# TOP.net
KiCad netlist of a schematic drawn in Altium Designer
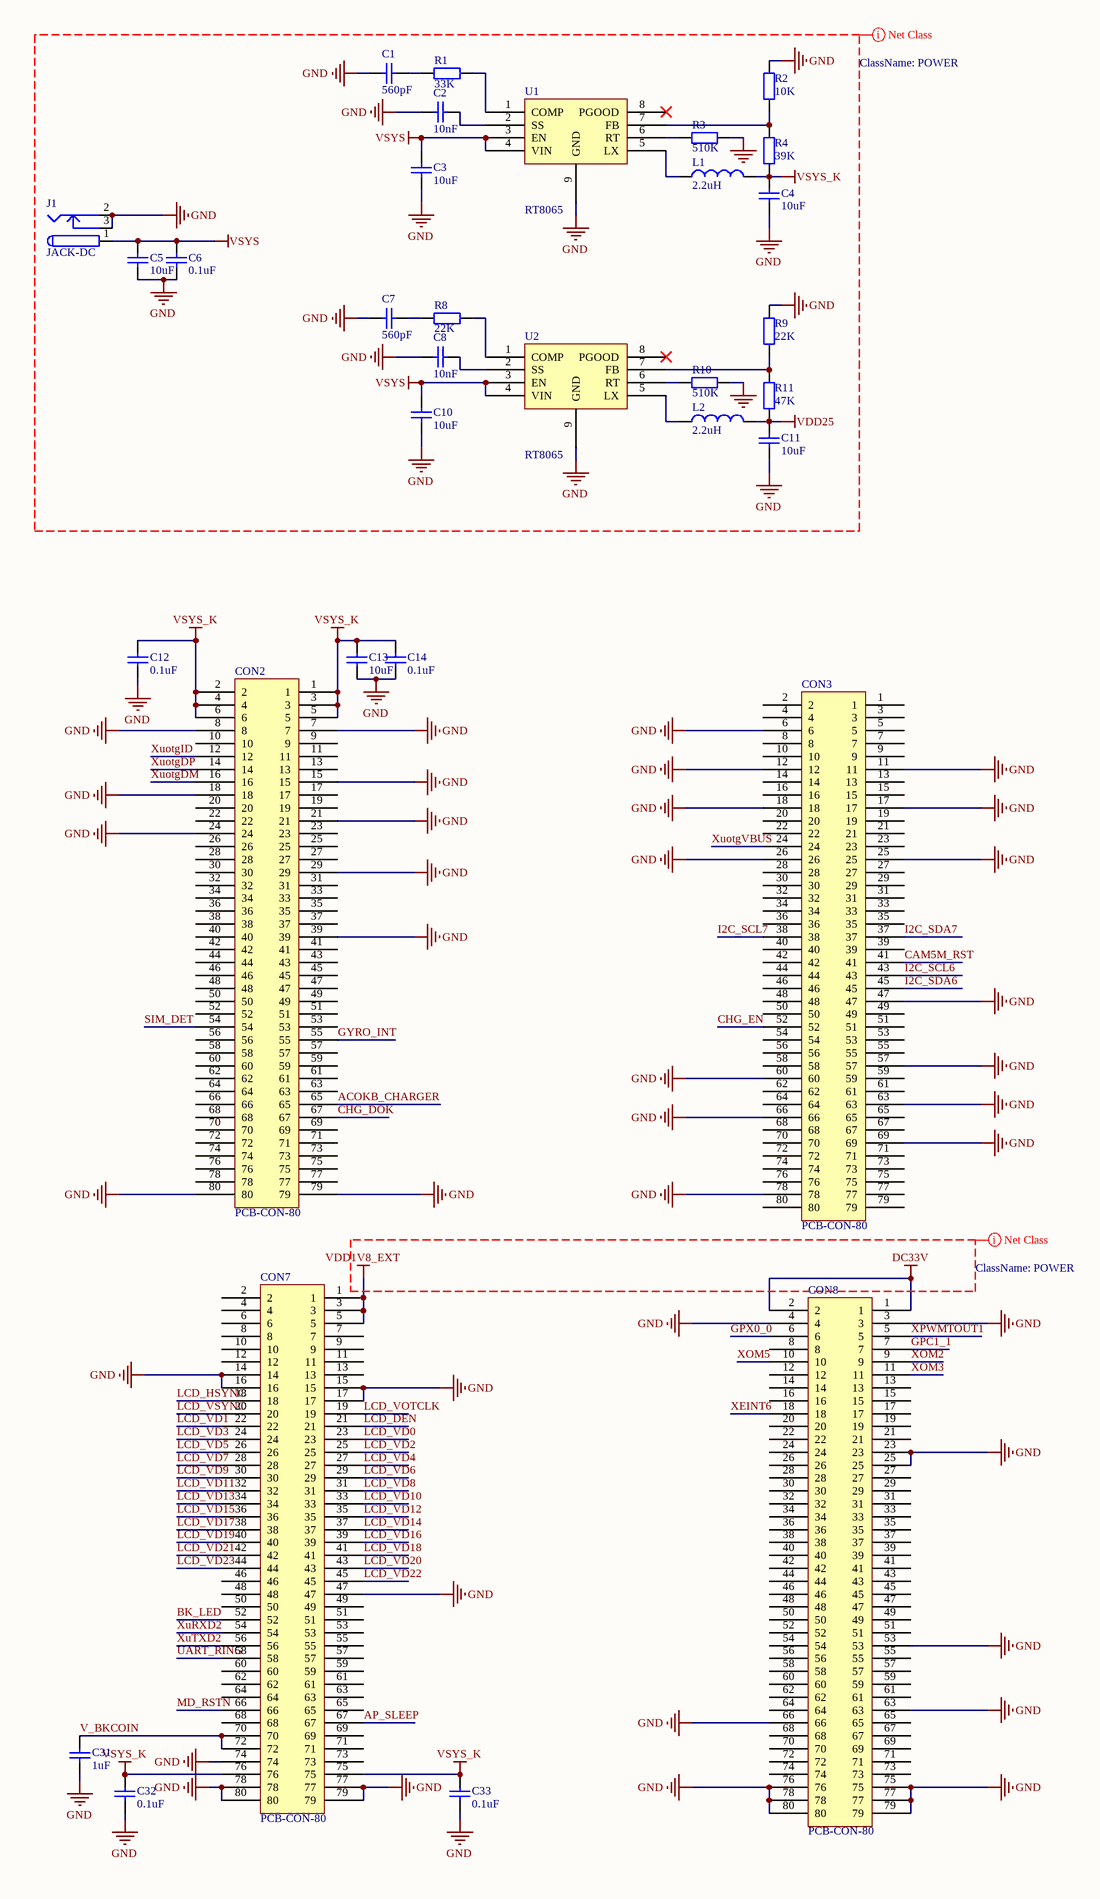
[diagram p0: TOP.SchDoc, left]
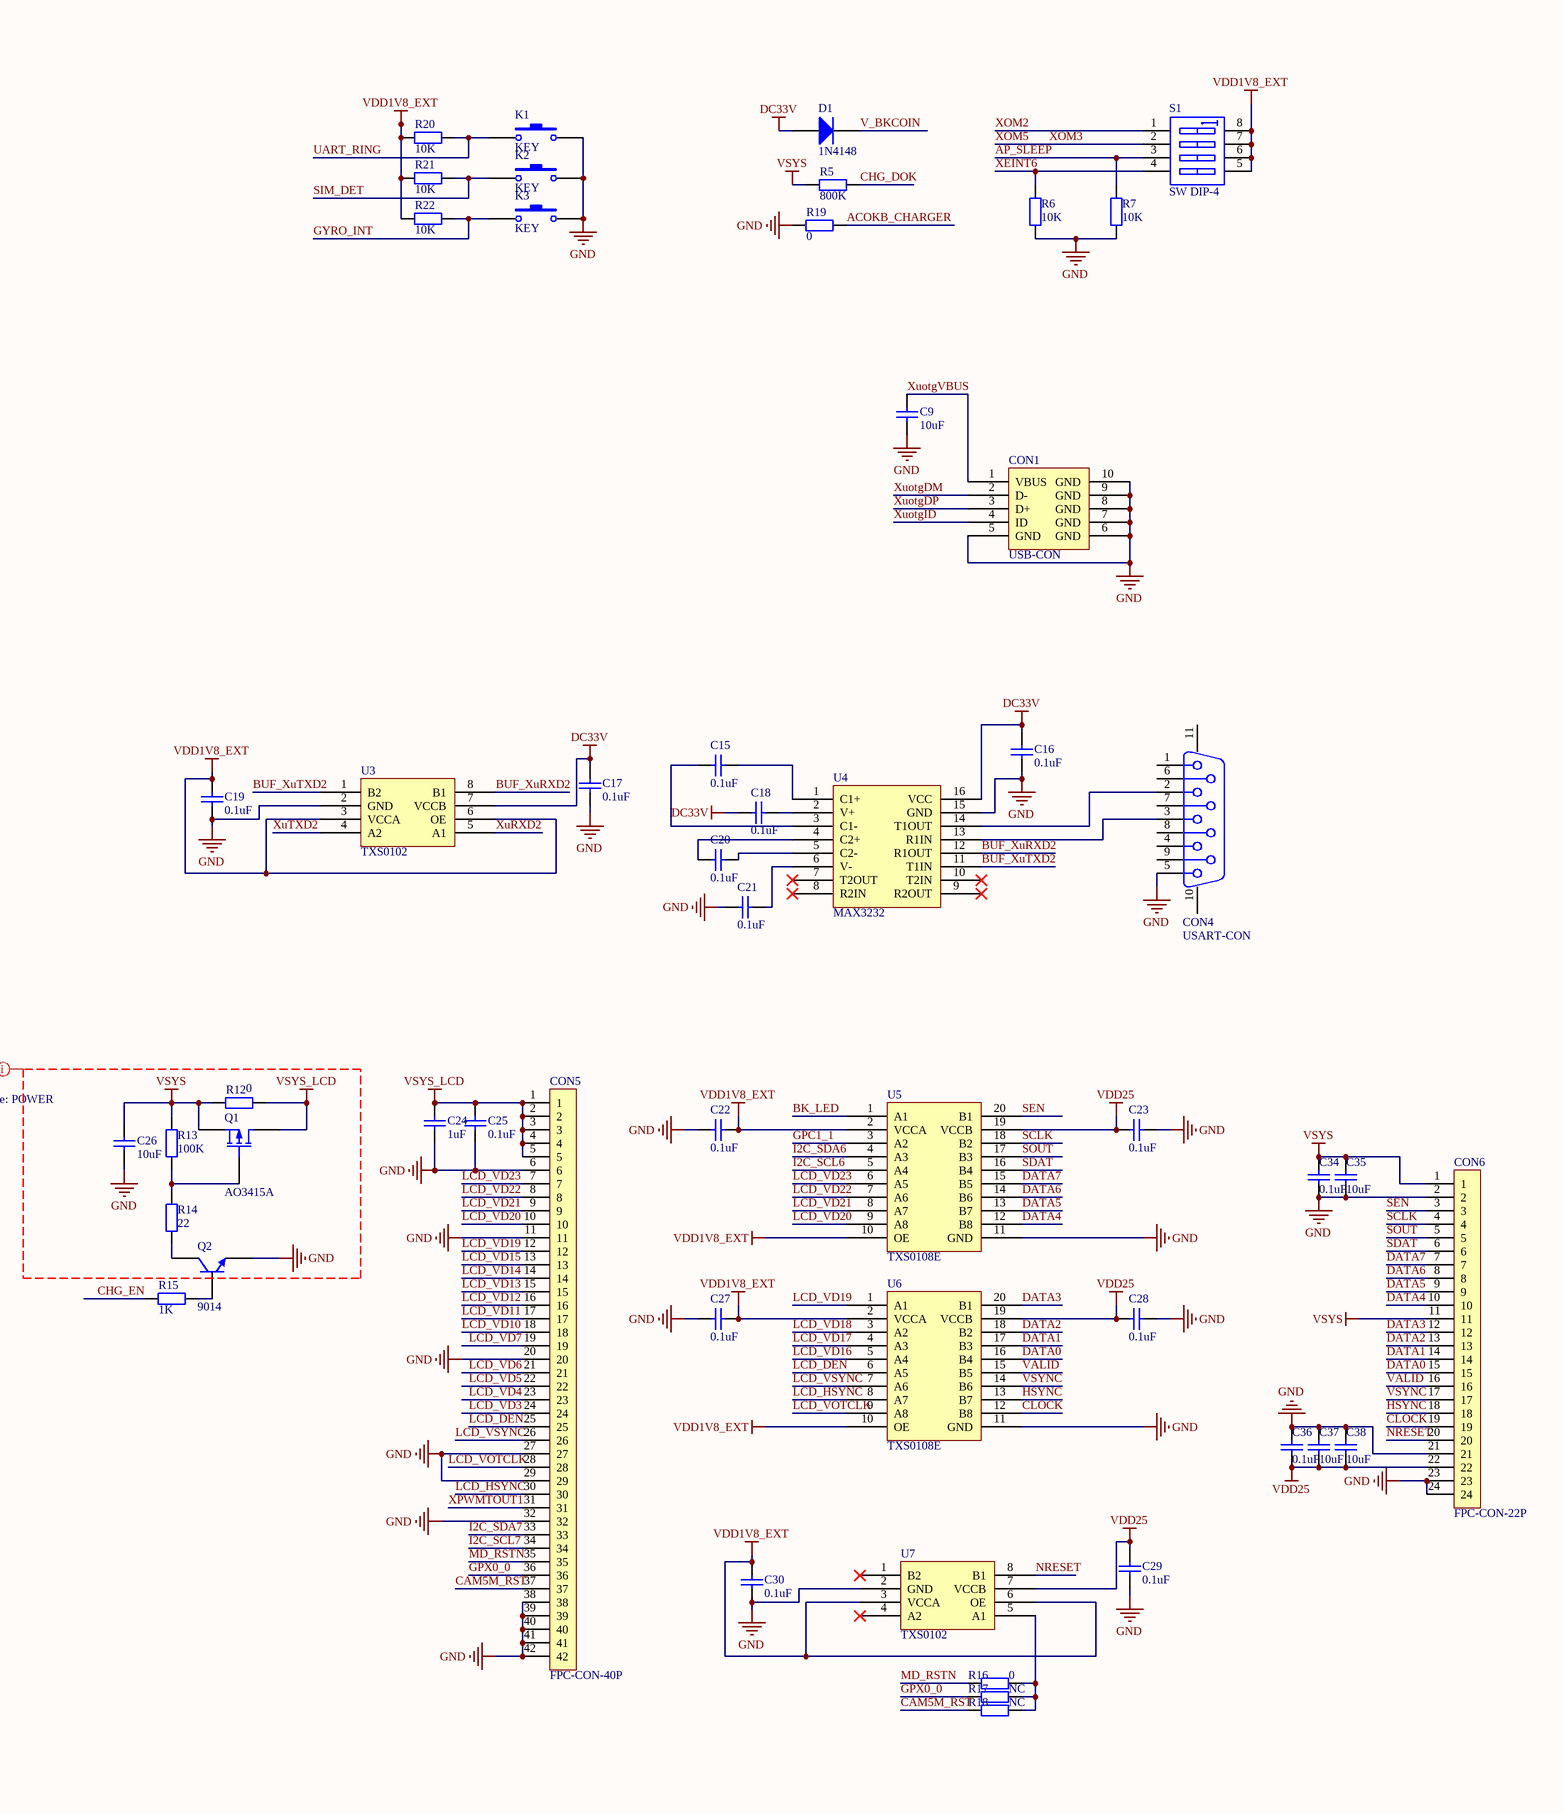
[diagram p1: TOP.SchDoc, right]

(export (version "E")
  (design (tool "Eeschema 10.0.6"))
  (components
    (comp (ref "C1")
      (value "560pF")
      (footprint "0603")
      (description "Capacitor")
      (fields (field (name "Comment") "Cap") (field (name "PUBLISHER") "Altium Limited"))
      (libsource (lib "Miscellaneous Devices") (part "Cap"))
    )
    (comp (ref "C2")
      (value "10nF")
      (footprint "0603")
      (description "Capacitor")
      (fields (field (name "Comment") "Cap") (field (name "PUBLISHER") "Altium Limited"))
      (libsource (lib "Miscellaneous Devices") (part "Cap"))
    )
    (comp (ref "C3")
      (value "10uF")
      (footprint "0805")
      (description "Capacitor")
      (fields (field (name "Comment") "Cap") (field (name "PUBLISHER") "Altium Limited"))
      (libsource (lib "Miscellaneous Devices") (part "Cap"))
    )
    (comp (ref "C4")
      (value "10uF")
      (footprint "0805")
      (description "Capacitor")
      (fields (field (name "Comment") "Cap") (field (name "PUBLISHER") "Altium Limited"))
      (libsource (lib "Miscellaneous Devices") (part "Cap"))
    )
    (comp (ref "C5")
      (value "10uF")
      (footprint "0805")
      (description "Capacitor")
      (fields (field (name "Comment") "Cap") (field (name "PUBLISHER") "Altium Limited"))
      (libsource (lib "Miscellaneous Devices") (part "Cap"))
    )
    (comp (ref "C6")
      (value "0.1uF")
      (footprint "0603")
      (description "Capacitor")
      (fields (field (name "Comment") "Cap") (field (name "PUBLISHER") "Altium Limited"))
      (libsource (lib "Miscellaneous Devices") (part "Cap"))
    )
    (comp (ref "C7")
      (value "560pF")
      (footprint "0603")
      (description "Capacitor")
      (fields (field (name "Comment") "Cap") (field (name "PUBLISHER") "Altium Limited"))
      (libsource (lib "Miscellaneous Devices") (part "Cap"))
    )
    (comp (ref "C8")
      (value "10nF")
      (footprint "0603")
      (description "Capacitor")
      (fields (field (name "Comment") "Cap") (field (name "PUBLISHER") "Altium Limited"))
      (libsource (lib "Miscellaneous Devices") (part "Cap"))
    )
    (comp (ref "C9")
      (value "10uF")
      (footprint "0805")
      (description "Capacitor")
      (fields (field (name "Comment") "Cap") (field (name "PUBLISHER") "Altium Limited"))
      (libsource (lib "Miscellaneous Devices") (part "Cap"))
    )
    (comp (ref "C10")
      (value "10uF")
      (footprint "0805")
      (description "Capacitor")
      (fields (field (name "Comment") "Cap") (field (name "PUBLISHER") "Altium Limited"))
      (libsource (lib "Miscellaneous Devices") (part "Cap"))
    )
    (comp (ref "C11")
      (value "10uF")
      (footprint "0805")
      (description "Capacitor")
      (fields (field (name "Comment") "Cap") (field (name "PUBLISHER") "Altium Limited"))
      (libsource (lib "Miscellaneous Devices") (part "Cap"))
    )
    (comp (ref "C12")
      (value "0.1uF")
      (footprint "0603")
      (description "Capacitor")
      (fields (field (name "Comment") "Cap") (field (name "PUBLISHER") "Altium Limited"))
      (libsource (lib "Miscellaneous Devices") (part "Cap"))
    )
    (comp (ref "C13")
      (value "10uF")
      (footprint "0805")
      (description "Capacitor")
      (fields (field (name "Comment") "Cap") (field (name "PUBLISHER") "Altium Limited"))
      (libsource (lib "Miscellaneous Devices") (part "Cap"))
    )
    (comp (ref "C14")
      (value "0.1uF")
      (footprint "0603")
      (description "Capacitor")
      (fields (field (name "Comment") "Cap") (field (name "PUBLISHER") "Altium Limited"))
      (libsource (lib "Miscellaneous Devices") (part "Cap"))
    )
    (comp (ref "C15")
      (value "0.1uF")
      (footprint "0603")
      (description "Capacitor")
      (fields (field (name "Comment") "Cap") (field (name "PUBLISHER") "Altium Limited"))
      (libsource (lib "Miscellaneous Devices") (part "Cap"))
    )
    (comp (ref "C16")
      (value "0.1uF")
      (footprint "0603")
      (description "Capacitor")
      (fields (field (name "Comment") "Cap") (field (name "PUBLISHER") "Altium Limited"))
      (libsource (lib "Miscellaneous Devices") (part "Cap"))
    )
    (comp (ref "C17")
      (value "0.1uF")
      (footprint "0603")
      (description "Capacitor")
      (fields (field (name "Comment") "Cap") (field (name "PUBLISHER") "Altium Limited"))
      (libsource (lib "Miscellaneous Devices") (part "Cap"))
    )
    (comp (ref "C18")
      (value "0.1uF")
      (footprint "0603")
      (description "Capacitor")
      (fields (field (name "Comment") "Cap") (field (name "PUBLISHER") "Altium Limited"))
      (libsource (lib "Miscellaneous Devices") (part "Cap"))
    )
    (comp (ref "C19")
      (value "0.1uF")
      (footprint "0603")
      (description "Capacitor")
      (fields (field (name "Comment") "Cap") (field (name "PUBLISHER") "Altium Limited"))
      (libsource (lib "Miscellaneous Devices") (part "Cap"))
    )
    (comp (ref "C20")
      (value "0.1uF")
      (footprint "0603")
      (description "Capacitor")
      (fields (field (name "Comment") "Cap") (field (name "PUBLISHER") "Altium Limited"))
      (libsource (lib "Miscellaneous Devices") (part "Cap"))
    )
    (comp (ref "C21")
      (value "0.1uF")
      (footprint "0603")
      (description "Capacitor")
      (fields (field (name "Comment") "Cap") (field (name "PUBLISHER") "Altium Limited"))
      (libsource (lib "Miscellaneous Devices") (part "Cap"))
    )
    (comp (ref "C22")
      (value "0.1uF")
      (footprint "0603")
      (description "Capacitor")
      (fields (field (name "Comment") "Cap") (field (name "PUBLISHER") "Altium Limited"))
      (libsource (lib "Miscellaneous Devices") (part "Cap"))
    )
    (comp (ref "C23")
      (value "0.1uF")
      (footprint "0603")
      (description "Capacitor")
      (fields (field (name "Comment") "Cap") (field (name "PUBLISHER") "Altium Limited"))
      (libsource (lib "Miscellaneous Devices") (part "Cap"))
    )
    (comp (ref "C24")
      (value "1uF")
      (footprint "0805")
      (description "Capacitor")
      (fields (field (name "Comment") "Cap") (field (name "PUBLISHER") "Altium Limited"))
      (libsource (lib "Miscellaneous Devices") (part "Cap"))
    )
    (comp (ref "C25")
      (value "0.1uF")
      (footprint "0603")
      (description "Capacitor")
      (fields (field (name "Comment") "Cap") (field (name "PUBLISHER") "Altium Limited"))
      (libsource (lib "Miscellaneous Devices") (part "Cap"))
    )
    (comp (ref "C26")
      (value "10uF")
      (footprint "0805")
      (description "Capacitor")
      (fields (field (name "Comment") "Cap") (field (name "PUBLISHER") "Altium Limited"))
      (libsource (lib "Miscellaneous Devices") (part "Cap"))
    )
    (comp (ref "C27")
      (value "0.1uF")
      (footprint "0603")
      (description "Capacitor")
      (fields (field (name "Comment") "Cap") (field (name "PUBLISHER") "Altium Limited"))
      (libsource (lib "Miscellaneous Devices") (part "Cap"))
    )
    (comp (ref "C28")
      (value "0.1uF")
      (footprint "0603")
      (description "Capacitor")
      (fields (field (name "Comment") "Cap") (field (name "PUBLISHER") "Altium Limited"))
      (libsource (lib "Miscellaneous Devices") (part "Cap"))
    )
    (comp (ref "C29")
      (value "0.1uF")
      (footprint "0603")
      (description "Capacitor")
      (fields (field (name "Comment") "Cap") (field (name "PUBLISHER") "Altium Limited"))
      (libsource (lib "Miscellaneous Devices") (part "Cap"))
    )
    (comp (ref "C30")
      (value "0.1uF")
      (footprint "0603")
      (description "Capacitor")
      (fields (field (name "Comment") "Cap") (field (name "PUBLISHER") "Altium Limited"))
      (libsource (lib "Miscellaneous Devices") (part "Cap"))
    )
    (comp (ref "C31")
      (value "1uF")
      (footprint "0805")
      (description "Capacitor")
      (fields (field (name "Comment") "Cap") (field (name "PUBLISHER") "Altium Limited"))
      (libsource (lib "Miscellaneous Devices") (part "Cap"))
    )
    (comp (ref "C32")
      (value "0.1uF")
      (footprint "0603")
      (description "Capacitor")
      (fields (field (name "Comment") "Cap") (field (name "PUBLISHER") "Altium Limited"))
      (libsource (lib "Miscellaneous Devices") (part "Cap"))
    )
    (comp (ref "C33")
      (value "0.1uF")
      (footprint "0603")
      (description "Capacitor")
      (fields (field (name "Comment") "Cap") (field (name "PUBLISHER") "Altium Limited"))
      (libsource (lib "Miscellaneous Devices") (part "Cap"))
    )
    (comp (ref "C34")
      (value "0.1uF")
      (footprint "0603")
      (description "Capacitor")
      (fields (field (name "Comment") "Cap") (field (name "PUBLISHER") "Altium Limited"))
      (libsource (lib "Miscellaneous Devices") (part "Cap"))
    )
    (comp (ref "C35")
      (value "10uF")
      (footprint "0805")
      (description "Capacitor")
      (fields (field (name "Comment") "Cap") (field (name "PUBLISHER") "Altium Limited"))
      (libsource (lib "Miscellaneous Devices") (part "Cap"))
    )
    (comp (ref "C36")
      (value "0.1uF")
      (footprint "0603")
      (description "Capacitor")
      (fields (field (name "Comment") "Cap") (field (name "PUBLISHER") "Altium Limited"))
      (libsource (lib "Miscellaneous Devices") (part "Cap"))
    )
    (comp (ref "C37")
      (value "10uF")
      (footprint "0805")
      (description "Capacitor")
      (fields (field (name "Comment") "Cap") (field (name "PUBLISHER") "Altium Limited"))
      (libsource (lib "Miscellaneous Devices") (part "Cap"))
    )
    (comp (ref "C38")
      (value "10uF")
      (footprint "0805")
      (description "Capacitor")
      (fields (field (name "Comment") "Cap") (field (name "PUBLISHER") "Altium Limited"))
      (libsource (lib "Miscellaneous Devices") (part "Cap"))
    )
    (comp (ref "CON1") (value "USB-CON") (footprint "USB-CON") (libsource (lib "Schlib1") (part "USB-CON")))
    (comp (ref "CON2")
      (value "PCB-CON-80")
      (footprint "PCB-CON-80")
      (libsource (lib "Schlib1") (part "PCB-CON-80"))
    )
    (comp (ref "CON3")
      (value "PCB-CON-80")
      (footprint "PCB-CON-80")
      (libsource (lib "Schlib1") (part "PCB-CON-80"))
    )
    (comp (ref "CON4")
      (value "USART-CON")
      (footprint "USART-CON")
      (libsource (lib "Schlib1") (part "USART-CON"))
    )
    (comp (ref "CON5")
      (value "FPC-CON-40P")
      (footprint "FPC-CON-40P")
      (libsource (lib "Schlib1") (part "FPC-CON-40P"))
    )
    (comp (ref "CON6")
      (value "FPC-CON-22P")
      (footprint "FPC-CON-22P")
      (libsource (lib "Schlib1") (part "FPC-CON-22P"))
    )
    (comp (ref "CON7")
      (value "PCB-CON-80")
      (footprint "PCB-CON-80")
      (libsource (lib "Schlib1") (part "PCB-CON-80"))
    )
    (comp (ref "CON8")
      (value "PCB-CON-80")
      (footprint "PCB-CON-80")
      (libsource (lib "Schlib1") (part "PCB-CON-80"))
    )
    (comp (ref "D1")
      (value "1N4148")
      (footprint "1206")
      (description "Default Diode")
      (fields (field (name "PUBLISHER") "Altium Limited"))
      (libsource (lib "Miscellaneous Devices") (part "Diode"))
    )
    (comp (ref "J1") (value "JACK-DC") (footprint "JACK-DC") (libsource (lib "Schlib1") (part "JACK-DC")))
    (comp (ref "K1")
      (value "KEY")
      (footprint "KEY(3*6*2.5)")
      (fields (field (name "PUBLISHER") "Altium Limited"))
      (libsource (lib "Schlib1") (part "KEY"))
    )
    (comp (ref "K2")
      (value "KEY")
      (footprint "KEY(3*6*2.5)")
      (fields (field (name "PUBLISHER") "Altium Limited"))
      (libsource (lib "Schlib1") (part "KEY"))
    )
    (comp (ref "K3")
      (value "KEY")
      (footprint "KEY(3*6*2.5)")
      (fields (field (name "PUBLISHER") "Altium Limited"))
      (libsource (lib "Schlib1") (part "KEY"))
    )
    (comp (ref "L1")
      (value "2.2uH")
      (footprint "1008")
      (description "Inductor")
      (fields (field (name "PUBLISHER") "Altium Limited"))
      (libsource (lib "Miscellaneous Devices") (part "Inductor"))
    )
    (comp (ref "L2")
      (value "2.2uH")
      (footprint "1008")
      (description "Inductor")
      (fields (field (name "PUBLISHER") "Altium Limited"))
      (libsource (lib "Miscellaneous Devices") (part "Inductor"))
    )
    (comp (ref "Q1") (value "AO3415A") (footprint "SOT-23") (libsource (lib "Schlib1") (part "AO3415A")))
    (comp (ref "Q2") (value "9014") (footprint "SOT-23") (libsource (lib "Schlib1") (part "9014")))
    (comp (ref "R1")
      (value "33K")
      (footprint "0603")
      (description "Resistor")
      (fields (field (name "Comment") "Res2") (field (name "PUBLISHER") "Altium Limited"))
      (libsource (lib "Miscellaneous Devices") (part "Res2"))
    )
    (comp (ref "R2")
      (value "10K")
      (footprint "0603")
      (description "Resistor")
      (fields (field (name "Comment") "Res2") (field (name "PUBLISHER") "Altium Limited"))
      (libsource (lib "") (part "Res2_1"))
    )
    (comp (ref "R3")
      (value "510K")
      (footprint "0603")
      (description "Resistor")
      (fields (field (name "Comment") "Res2") (field (name "PUBLISHER") "Altium Limited"))
      (libsource (lib "Miscellaneous Devices") (part "Res2"))
    )
    (comp (ref "R4")
      (value "39K")
      (footprint "0603")
      (description "Resistor")
      (fields (field (name "Comment") "Res2") (field (name "PUBLISHER") "Altium Limited"))
      (libsource (lib "") (part "Res2_1"))
    )
    (comp (ref "R5")
      (value "800K")
      (footprint "0603")
      (description "Resistor")
      (fields (field (name "Comment") "Res2") (field (name "PUBLISHER") "Altium Limited"))
      (libsource (lib "Miscellaneous Devices") (part "Res2"))
    )
    (comp (ref "R6")
      (value "10K")
      (footprint "0603")
      (description "Resistor")
      (fields (field (name "Comment") "Res2") (field (name "PUBLISHER") "Altium Limited"))
      (libsource (lib "") (part "Res2_2"))
    )
    (comp (ref "R7")
      (value "10K")
      (footprint "0603")
      (description "Resistor")
      (fields (field (name "Comment") "Res2") (field (name "PUBLISHER") "Altium Limited"))
      (libsource (lib "") (part "Res2_1"))
    )
    (comp (ref "R8")
      (value "22K")
      (footprint "0603")
      (description "Resistor")
      (fields (field (name "Comment") "Res2") (field (name "PUBLISHER") "Altium Limited"))
      (libsource (lib "Miscellaneous Devices") (part "Res2"))
    )
    (comp (ref "R9")
      (value "22K")
      (footprint "0603")
      (description "Resistor")
      (fields (field (name "Comment") "Res2") (field (name "PUBLISHER") "Altium Limited"))
      (libsource (lib "") (part "Res2_1"))
    )
    (comp (ref "R10")
      (value "510K")
      (footprint "0603")
      (description "Resistor")
      (fields (field (name "Comment") "Res2") (field (name "PUBLISHER") "Altium Limited"))
      (libsource (lib "Miscellaneous Devices") (part "Res2"))
    )
    (comp (ref "R11")
      (value "47K")
      (footprint "0603")
      (description "Resistor")
      (fields (field (name "Comment") "Res2") (field (name "PUBLISHER") "Altium Limited"))
      (libsource (lib "") (part "Res2_1"))
    )
    (comp (ref "R12")
      (value "0")
      (footprint "0603")
      (description "Resistor")
      (fields (field (name "Comment") "Res2") (field (name "PUBLISHER") "Altium Limited"))
      (libsource (lib "Miscellaneous Devices") (part "Res2"))
    )
    (comp (ref "R13")
      (value "100K")
      (footprint "0603")
      (description "Resistor")
      (fields (field (name "Comment") "Res2") (field (name "PUBLISHER") "Altium Limited"))
      (libsource (lib "") (part "Res2_1"))
    )
    (comp (ref "R14")
      (value "22")
      (footprint "0603")
      (description "Resistor")
      (fields (field (name "Comment") "Res2") (field (name "PUBLISHER") "Altium Limited"))
      (libsource (lib "") (part "Res2_1"))
    )
    (comp (ref "R15")
      (value "1K")
      (footprint "0603")
      (description "Resistor")
      (fields (field (name "Comment") "Res2") (field (name "PUBLISHER") "Altium Limited"))
      (libsource (lib "Miscellaneous Devices") (part "Res2"))
    )
    (comp (ref "R16")
      (value "0")
      (footprint "0603")
      (description "Resistor")
      (fields (field (name "Comment") "Res2") (field (name "PUBLISHER") "Altium Limited"))
      (libsource (lib "Miscellaneous Devices") (part "Res2"))
    )
    (comp (ref "R17")
      (value "NC")
      (footprint "0603")
      (description "Resistor")
      (fields (field (name "Comment") "Res2") (field (name "PUBLISHER") "Altium Limited"))
      (libsource (lib "Miscellaneous Devices") (part "Res2"))
    )
    (comp (ref "R18")
      (value "NC")
      (footprint "0603")
      (description "Resistor")
      (fields (field (name "Comment") "Res2") (field (name "PUBLISHER") "Altium Limited"))
      (libsource (lib "Miscellaneous Devices") (part "Res2"))
    )
    (comp (ref "R19")
      (value "0")
      (footprint "0603")
      (description "Resistor")
      (fields (field (name "Comment") "Res2") (field (name "PUBLISHER") "Altium Limited"))
      (libsource (lib "Miscellaneous Devices") (part "Res2"))
    )
    (comp (ref "R20")
      (value "10K")
      (footprint "0603")
      (description "Resistor")
      (fields (field (name "Comment") "Res2") (field (name "PUBLISHER") "Altium Limited"))
      (libsource (lib "Miscellaneous Devices") (part "Res2"))
    )
    (comp (ref "R21")
      (value "10K")
      (footprint "0603")
      (description "Resistor")
      (fields (field (name "Comment") "Res2") (field (name "PUBLISHER") "Altium Limited"))
      (libsource (lib "Miscellaneous Devices") (part "Res2"))
    )
    (comp (ref "R22")
      (value "10K")
      (footprint "0603")
      (description "Resistor")
      (fields (field (name "Comment") "Res2") (field (name "PUBLISHER") "Altium Limited"))
      (libsource (lib "Miscellaneous Devices") (part "Res2"))
    )
    (comp (ref "S1")
      (value "SW DIP-4")
      (footprint "SW-4")
      (description "DIP Switch, 4 Position, SPST")
      (fields (field (name "PUBLISHER") "Altium Limited"))
      (libsource (lib "Miscellaneous Devices") (part "SW DIP-4"))
    )
    (comp (ref "U1") (value "RT8065") (footprint "RT8065(SOP8)") (libsource (lib "Schlib1") (part "RT8065")))
    (comp (ref "U2") (value "RT8065") (footprint "RT8065(SOP8)") (libsource (lib "Schlib1") (part "RT8065")))
    (comp (ref "U3")
      (value "TXS0102")
      (footprint "TXS0102(SOP8)")
      (libsource (lib "Schlib1") (part "TXS0102"))
    )
    (comp (ref "U4")
      (value "MAX3232")
      (footprint "MAX3232(SOP16)")
      (libsource (lib "Schlib1") (part "MAX3232"))
    )
    (comp (ref "U5")
      (value "TXS0108E")
      (footprint "TXS0108E(SOP20)")
      (libsource (lib "Schlib1") (part "TXS0108E"))
    )
    (comp (ref "U6")
      (value "TXS0108E")
      (footprint "TXS0108E(SOP20)")
      (libsource (lib "Schlib1") (part "TXS0108E"))
    )
    (comp (ref "U7")
      (value "TXS0102")
      (footprint "TXS0102(SOP8)")
      (libsource (lib "Schlib1") (part "TXS0102"))
    )
  )
  (nets
    (net (code "1") (name "/ACOKB_CHARGER") (class "Default")
      (node (ref "CON2") (pin "65") (pinfunction "65_65") (pintype "passive"))
      (node (ref "R19") (pin "2") (pinfunction "2_2") (pintype "passive"))
    )
    (net (code "2") (name "/AP_SLEEP") (class "Default")
      (node (ref "CON7") (pin "67") (pinfunction "67_67") (pintype "passive"))
      (node (ref "R7") (pin "2") (pinfunction "2_2") (pintype "passive"))
      (node (ref "S1") (pin "3") (pinfunction "A3_3") (pintype "passive"))
    )
    (net (code "3") (name "/BK_LED") (class "Default")
      (node (ref "CON7") (pin "52") (pinfunction "52_52") (pintype "passive"))
      (node (ref "U5") (pin "1") (pinfunction "A1_1") (pintype "passive"))
    )
    (net (code "4") (name "/BUF_XuRXD2") (class "Default")
      (node (ref "U3") (pin "8") (pinfunction "B1_8") (pintype "passive"))
      (node (ref "U4") (pin "12") (pinfunction "R1OUT_12") (pintype "passive"))
    )
    (net (code "5") (name "/BUF_XuTXD2") (class "Default")
      (node (ref "U3") (pin "1") (pinfunction "B2_1") (pintype "passive"))
      (node (ref "U4") (pin "11") (pinfunction "T1IN_11") (pintype "passive"))
    )
    (net (code "6") (name "/CAM5M_RST") (class "Default")
      (node (ref "CON3") (pin "41") (pinfunction "41_41") (pintype "passive"))
      (node (ref "CON5") (pin "37") (pinfunction "37_37") (pintype "passive"))
      (node (ref "R18") (pin "1") (pinfunction "1_1") (pintype "passive"))
    )
    (net (code "7") (name "/CHG_DOK") (class "Default")
      (node (ref "CON2") (pin "67") (pinfunction "67_67") (pintype "passive"))
      (node (ref "R5") (pin "2") (pinfunction "2_2") (pintype "passive"))
    )
    (net (code "8") (name "/CHG_EN") (class "Default")
      (node (ref "CON3") (pin "52") (pinfunction "52_52") (pintype "passive"))
      (node (ref "R15") (pin "1") (pinfunction "1_1") (pintype "passive"))
    )
    (net (code "9") (name "/CLOCK") (class "Default")
      (node (ref "CON6") (pin "19") (pinfunction "19_19") (pintype "passive"))
      (node (ref "U6") (pin "12") (pinfunction "B8_12") (pintype "passive"))
    )
    (net (code "10") (name "/DATA0") (class "Default")
      (node (ref "CON6") (pin "15") (pinfunction "15_15") (pintype "passive"))
      (node (ref "U6") (pin "16") (pinfunction "B4_16") (pintype "passive"))
    )
    (net (code "11") (name "/DATA1") (class "Default")
      (node (ref "CON6") (pin "14") (pinfunction "14_14") (pintype "passive"))
      (node (ref "U6") (pin "17") (pinfunction "B3_17") (pintype "passive"))
    )
    (net (code "12") (name "/DATA2") (class "Default")
      (node (ref "CON6") (pin "13") (pinfunction "13_13") (pintype "passive"))
      (node (ref "U6") (pin "18") (pinfunction "B2_18") (pintype "passive"))
    )
    (net (code "13") (name "/DATA3") (class "Default")
      (node (ref "CON6") (pin "12") (pinfunction "12_12") (pintype "passive"))
      (node (ref "U6") (pin "20") (pinfunction "B1_20") (pintype "passive"))
    )
    (net (code "14") (name "/DATA4") (class "Default")
      (node (ref "CON6") (pin "10") (pinfunction "10_10") (pintype "passive"))
      (node (ref "U5") (pin "12") (pinfunction "B8_12") (pintype "passive"))
    )
    (net (code "15") (name "/DATA5") (class "Default")
      (node (ref "CON6") (pin "9") (pinfunction "9_9") (pintype "passive"))
      (node (ref "U5") (pin "13") (pinfunction "B7_13") (pintype "passive"))
    )
    (net (code "16") (name "/DATA6") (class "Default")
      (node (ref "CON6") (pin "8") (pinfunction "8_8") (pintype "passive"))
      (node (ref "U5") (pin "14") (pinfunction "B6_14") (pintype "passive"))
    )
    (net (code "17") (name "/DATA7") (class "Default")
      (node (ref "CON6") (pin "7") (pinfunction "7_7") (pintype "passive"))
      (node (ref "U5") (pin "15") (pinfunction "B5_15") (pintype "passive"))
    )
    (net (code "18") (name "/GPC1_1") (class "Default")
      (node (ref "CON8") (pin "7") (pinfunction "7_7") (pintype "passive"))
      (node (ref "U5") (pin "3") (pinfunction "A2_3") (pintype "passive"))
    )
    (net (code "19") (name "/GPX0_0") (class "Default")
      (node (ref "CON5") (pin "36") (pinfunction "36_36") (pintype "passive"))
      (node (ref "CON8") (pin "6") (pinfunction "6_6") (pintype "passive"))
      (node (ref "R17") (pin "1") (pinfunction "1_1") (pintype "passive"))
    )
    (net (code "20") (name "/GYRO_INT") (class "Default")
      (node (ref "CON2") (pin "55") (pinfunction "55_55") (pintype "passive"))
      (node (ref "K3") (pin "1") (pinfunction "1_1") (pintype "passive"))
      (node (ref "R22") (pin "2") (pinfunction "2_2") (pintype "passive"))
    )
    (net (code "21") (name "/HSYNC") (class "Default")
      (node (ref "CON6") (pin "18") (pinfunction "18_18") (pintype "passive"))
      (node (ref "U6") (pin "13") (pinfunction "B7_13") (pintype "passive"))
    )
    (net (code "22") (name "/I2C_SCL6") (class "Default")
      (node (ref "CON3") (pin "43") (pinfunction "43_43") (pintype "passive"))
      (node (ref "U5") (pin "5") (pinfunction "A4_5") (pintype "passive"))
    )
    (net (code "23") (name "/I2C_SCL7") (class "Default")
      (node (ref "CON3") (pin "38") (pinfunction "38_38") (pintype "passive"))
      (node (ref "CON5") (pin "34") (pinfunction "34_34") (pintype "passive"))
    )
    (net (code "24") (name "/I2C_SDA6") (class "Default")
      (node (ref "CON3") (pin "45") (pinfunction "45_45") (pintype "passive"))
      (node (ref "U5") (pin "4") (pinfunction "A3_4") (pintype "passive"))
    )
    (net (code "25") (name "/I2C_SDA7") (class "Default")
      (node (ref "CON3") (pin "37") (pinfunction "37_37") (pintype "passive"))
      (node (ref "CON5") (pin "33") (pinfunction "33_33") (pintype "passive"))
    )
    (net (code "26") (name "/LCD_DEN") (class "Default")
      (node (ref "CON5") (pin "25") (pinfunction "25_25") (pintype "passive"))
      (node (ref "CON7") (pin "21") (pinfunction "21_21") (pintype "passive"))
      (node (ref "U6") (pin "6") (pinfunction "A5_6") (pintype "passive"))
    )
    (net (code "27") (name "/LCD_HSYNC") (class "Default")
      (node (ref "CON5") (pin "30") (pinfunction "30_30") (pintype "passive"))
      (node (ref "CON7") (pin "18") (pinfunction "18_18") (pintype "passive"))
      (node (ref "U6") (pin "8") (pinfunction "A7_8") (pintype "passive"))
    )
    (net (code "28") (name "/LCD_VD0") (class "Default")
      (node (ref "CON7") (pin "23") (pinfunction "23_23") (pintype "passive"))
    )
    (net (code "29") (name "/LCD_VD1") (class "Default")
      (node (ref "CON7") (pin "22") (pinfunction "22_22") (pintype "passive"))
    )
    (net (code "30") (name "/LCD_VD2") (class "Default")
      (node (ref "CON7") (pin "25") (pinfunction "25_25") (pintype "passive"))
    )
    (net (code "31") (name "/LCD_VD3") (class "Default")
      (node (ref "CON5") (pin "24") (pinfunction "24_24") (pintype "passive"))
      (node (ref "CON7") (pin "24") (pinfunction "24_24") (pintype "passive"))
    )
    (net (code "32") (name "/LCD_VD4") (class "Default")
      (node (ref "CON5") (pin "23") (pinfunction "23_23") (pintype "passive"))
      (node (ref "CON7") (pin "27") (pinfunction "27_27") (pintype "passive"))
    )
    (net (code "33") (name "/LCD_VD5") (class "Default")
      (node (ref "CON5") (pin "22") (pinfunction "22_22") (pintype "passive"))
      (node (ref "CON7") (pin "26") (pinfunction "26_26") (pintype "passive"))
    )
    (net (code "34") (name "/LCD_VD6") (class "Default")
      (node (ref "CON5") (pin "21") (pinfunction "21_21") (pintype "passive"))
      (node (ref "CON7") (pin "29") (pinfunction "29_29") (pintype "passive"))
    )
    (net (code "35") (name "/LCD_VD7") (class "Default")
      (node (ref "CON5") (pin "19") (pinfunction "19_19") (pintype "passive"))
      (node (ref "CON7") (pin "28") (pinfunction "28_28") (pintype "passive"))
    )
    (net (code "36") (name "/LCD_VD8") (class "Default")
      (node (ref "CON7") (pin "31") (pinfunction "31_31") (pintype "passive"))
    )
    (net (code "37") (name "/LCD_VD9") (class "Default")
      (node (ref "CON7") (pin "30") (pinfunction "30_30") (pintype "passive"))
    )
    (net (code "38") (name "/LCD_VD10") (class "Default")
      (node (ref "CON5") (pin "18") (pinfunction "18_18") (pintype "passive"))
      (node (ref "CON7") (pin "33") (pinfunction "33_33") (pintype "passive"))
    )
    (net (code "39") (name "/LCD_VD11") (class "Default")
      (node (ref "CON5") (pin "17") (pinfunction "17_17") (pintype "passive"))
      (node (ref "CON7") (pin "32") (pinfunction "32_32") (pintype "passive"))
    )
    (net (code "40") (name "/LCD_VD12") (class "Default")
      (node (ref "CON5") (pin "16") (pinfunction "16_16") (pintype "passive"))
      (node (ref "CON7") (pin "35") (pinfunction "35_35") (pintype "passive"))
    )
    (net (code "41") (name "/LCD_VD13") (class "Default")
      (node (ref "CON5") (pin "15") (pinfunction "15_15") (pintype "passive"))
      (node (ref "CON7") (pin "34") (pinfunction "34_34") (pintype "passive"))
    )
    (net (code "42") (name "/LCD_VD14") (class "Default")
      (node (ref "CON5") (pin "14") (pinfunction "14_14") (pintype "passive"))
      (node (ref "CON7") (pin "37") (pinfunction "37_37") (pintype "passive"))
    )
    (net (code "43") (name "/LCD_VD15") (class "Default")
      (node (ref "CON5") (pin "13") (pinfunction "13_13") (pintype "passive"))
      (node (ref "CON7") (pin "36") (pinfunction "36_36") (pintype "passive"))
    )
    (net (code "44") (name "/LCD_VD16") (class "Default")
      (node (ref "CON7") (pin "39") (pinfunction "39_39") (pintype "passive"))
      (node (ref "U6") (pin "5") (pinfunction "A4_5") (pintype "passive"))
    )
    (net (code "45") (name "/LCD_VD17") (class "Default")
      (node (ref "CON7") (pin "38") (pinfunction "38_38") (pintype "passive"))
      (node (ref "U6") (pin "4") (pinfunction "A3_4") (pintype "passive"))
    )
    (net (code "46") (name "/LCD_VD18") (class "Default")
      (node (ref "CON7") (pin "41") (pinfunction "41_41") (pintype "passive"))
      (node (ref "U6") (pin "3") (pinfunction "A2_3") (pintype "passive"))
    )
    (net (code "47") (name "/LCD_VD19") (class "Default")
      (node (ref "CON5") (pin "12") (pinfunction "12_12") (pintype "passive"))
      (node (ref "CON7") (pin "40") (pinfunction "40_40") (pintype "passive"))
      (node (ref "U6") (pin "1") (pinfunction "A1_1") (pintype "passive"))
    )
    (net (code "48") (name "/LCD_VD20") (class "Default")
      (node (ref "CON5") (pin "10") (pinfunction "10_10") (pintype "passive"))
      (node (ref "CON7") (pin "43") (pinfunction "43_43") (pintype "passive"))
      (node (ref "U5") (pin "9") (pinfunction "A8_9") (pintype "passive"))
    )
    (net (code "49") (name "/LCD_VD21") (class "Default")
      (node (ref "CON5") (pin "9") (pinfunction "9_9") (pintype "passive"))
      (node (ref "CON7") (pin "42") (pinfunction "42_42") (pintype "passive"))
      (node (ref "U5") (pin "8") (pinfunction "A7_8") (pintype "passive"))
    )
    (net (code "50") (name "/LCD_VD22") (class "Default")
      (node (ref "CON5") (pin "8") (pinfunction "8_8") (pintype "passive"))
      (node (ref "CON7") (pin "45") (pinfunction "45_45") (pintype "passive"))
      (node (ref "U5") (pin "7") (pinfunction "A6_7") (pintype "passive"))
    )
    (net (code "51") (name "/LCD_VD23") (class "Default")
      (node (ref "CON5") (pin "7") (pinfunction "7_7") (pintype "passive"))
      (node (ref "CON7") (pin "44") (pinfunction "44_44") (pintype "passive"))
      (node (ref "U5") (pin "6") (pinfunction "A5_6") (pintype "passive"))
    )
    (net (code "52") (name "/LCD_VOTCLK") (class "Default")
      (node (ref "CON5") (pin "28") (pinfunction "28_28") (pintype "passive"))
      (node (ref "CON7") (pin "19") (pinfunction "19_19") (pintype "passive"))
      (node (ref "U6") (pin "9") (pinfunction "A8_9") (pintype "passive"))
    )
    (net (code "53") (name "/LCD_VSYNC") (class "Default")
      (node (ref "CON5") (pin "26") (pinfunction "26_26") (pintype "passive"))
      (node (ref "CON7") (pin "20") (pinfunction "20_20") (pintype "passive"))
      (node (ref "U6") (pin "7") (pinfunction "A6_7") (pintype "passive"))
    )
    (net (code "54") (name "/MD_RSTN") (class "Default")
      (node (ref "CON5") (pin "35") (pinfunction "35_35") (pintype "passive"))
      (node (ref "CON7") (pin "66") (pinfunction "66_66") (pintype "passive"))
      (node (ref "R16") (pin "1") (pinfunction "1_1") (pintype "passive"))
    )
    (net (code "55") (name "/NRESET") (class "Default")
      (node (ref "CON6") (pin "20") (pinfunction "20_20") (pintype "passive"))
      (node (ref "U7") (pin "8") (pinfunction "B1_8") (pintype "passive"))
    )
    (net (code "56") (name "/SCLK") (class "Default")
      (node (ref "CON6") (pin "4") (pinfunction "4_4") (pintype "passive"))
      (node (ref "U5") (pin "18") (pinfunction "B2_18") (pintype "passive"))
    )
    (net (code "57") (name "/SDAT") (class "Default")
      (node (ref "CON6") (pin "6") (pinfunction "6_6") (pintype "passive"))
      (node (ref "U5") (pin "16") (pinfunction "B4_16") (pintype "passive"))
    )
    (net (code "58") (name "/SEN") (class "Default")
      (node (ref "CON6") (pin "3") (pinfunction "3_3") (pintype "passive"))
      (node (ref "U5") (pin "20") (pinfunction "B1_20") (pintype "passive"))
    )
    (net (code "59") (name "/SIM_DET") (class "Default")
      (node (ref "CON2") (pin "54") (pinfunction "54_54") (pintype "passive"))
      (node (ref "K2") (pin "1") (pinfunction "1_1") (pintype "passive"))
      (node (ref "R21") (pin "2") (pinfunction "2_2") (pintype "passive"))
    )
    (net (code "60") (name "/SOUT") (class "Default")
      (node (ref "CON6") (pin "5") (pinfunction "5_5") (pintype "passive"))
      (node (ref "U5") (pin "17") (pinfunction "B3_17") (pintype "passive"))
    )
    (net (code "61") (name "/UART_RING") (class "Default")
      (node (ref "CON7") (pin "58") (pinfunction "58_58") (pintype "passive"))
      (node (ref "K1") (pin "1") (pinfunction "1_1") (pintype "passive"))
      (node (ref "R20") (pin "2") (pinfunction "2_2") (pintype "passive"))
    )
    (net (code "62") (name "/VALID") (class "Default")
      (node (ref "CON6") (pin "16") (pinfunction "16_16") (pintype "passive"))
      (node (ref "U6") (pin "15") (pinfunction "B5_15") (pintype "passive"))
    )
    (net (code "63") (name "/VSYNC") (class "Default")
      (node (ref "CON6") (pin "17") (pinfunction "17_17") (pintype "passive"))
      (node (ref "U6") (pin "14") (pinfunction "B6_14") (pintype "passive"))
    )
    (net (code "64") (name "/V_BKCOIN") (class "Default")
      (node (ref "C31") (pin "1") (pinfunction "1_1") (pintype "passive"))
      (node (ref "CON7") (pin "70") (pinfunction "70_70") (pintype "passive"))
      (node (ref "CON7") (pin "72") (pinfunction "72_72") (pintype "passive"))
      (node (ref "D1") (pin "2") (pinfunction "K_2") (pintype "passive"))
    )
    (net (code "65") (name "/XEINT6") (class "Default")
      (node (ref "CON8") (pin "18") (pinfunction "18_18") (pintype "passive"))
      (node (ref "R6") (pin "1") (pinfunction "1_1") (pintype "passive"))
      (node (ref "S1") (pin "4") (pinfunction "A4_4") (pintype "passive"))
    )
    (net (code "66") (name "/XOM2") (class "Default")
      (node (ref "CON8") (pin "9") (pinfunction "9_9") (pintype "passive"))
      (node (ref "S1") (pin "1") (pinfunction "A1_1") (pintype "passive"))
    )
    (net (code "67") (name "/XOM3") (class "Default")
      (node (ref "CON8") (pin "10") (pinfunction "10_10") (pintype "passive"))
      (node (ref "CON8") (pin "11") (pinfunction "11_11") (pintype "passive"))
      (node (ref "S1") (pin "2") (pinfunction "A2_2") (pintype "passive"))
    )
    (net (code "68") (name "/XPWMTOUT1") (class "Default")
      (node (ref "CON5") (pin "31") (pinfunction "31_31") (pintype "passive"))
      (node (ref "CON8") (pin "5") (pinfunction "5_5") (pintype "passive"))
    )
    (net (code "69") (name "/XuRXD2") (class "Default")
      (node (ref "CON7") (pin "54") (pinfunction "54_54") (pintype "passive"))
      (node (ref "U3") (pin "5") (pinfunction "A1_5") (pintype "passive"))
    )
    (net (code "70") (name "/XuTXD2") (class "Default")
      (node (ref "CON7") (pin "56") (pinfunction "56_56") (pintype "passive"))
      (node (ref "U3") (pin "4") (pinfunction "A2_4") (pintype "passive"))
    )
    (net (code "71") (name "/XuotgDM") (class "Default")
      (node (ref "CON1") (pin "2") (pinfunction "D-_2") (pintype "passive"))
      (node (ref "CON2") (pin "16") (pinfunction "16_16") (pintype "passive"))
    )
    (net (code "72") (name "/XuotgDP") (class "Default")
      (node (ref "CON1") (pin "3") (pinfunction "D+_3") (pintype "passive"))
      (node (ref "CON2") (pin "14") (pinfunction "14_14") (pintype "passive"))
    )
    (net (code "73") (name "/XuotgID") (class "Default")
      (node (ref "CON1") (pin "4") (pinfunction "ID_4") (pintype "passive"))
      (node (ref "CON2") (pin "12") (pinfunction "12_12") (pintype "passive"))
    )
    (net (code "74") (name "/XuotgVBUS") (class "Default")
      (node (ref "C9") (pin "2") (pinfunction "2_2") (pintype "passive"))
      (node (ref "CON1") (pin "1") (pinfunction "VBUS_1") (pintype "passive"))
      (node (ref "CON3") (pin "24") (pinfunction "24_24") (pintype "passive"))
    )
    (net (code "75") (name "DC33V") (class "Default")
      (node (ref "C16") (pin "1") (pinfunction "1_1") (pintype "passive"))
      (node (ref "C17") (pin "2") (pinfunction "2_2") (pintype "passive"))
      (node (ref "C18") (pin "1") (pinfunction "1_1") (pintype "passive"))
      (node (ref "CON8") (pin "1") (pinfunction "1_1") (pintype "passive"))
      (node (ref "CON8") (pin "2") (pinfunction "2_2") (pintype "passive"))
      (node (ref "D1") (pin "1") (pinfunction "A_1") (pintype "passive"))
      (node (ref "U3") (pin "7") (pinfunction "VCCB_7") (pintype "passive"))
      (node (ref "U4") (pin "16") (pinfunction "VCC_16") (pintype "passive"))
    )
    (net (code "76") (name "GND") (class "Default")
      (node (ref "C1") (pin "2") (pinfunction "2_2") (pintype "passive"))
      (node (ref "C10") (pin "1") (pinfunction "1_1") (pintype "passive"))
      (node (ref "C11") (pin "1") (pinfunction "1_1") (pintype "passive"))
      (node (ref "C12") (pin "2") (pinfunction "2_2") (pintype "passive"))
      (node (ref "C13") (pin "1") (pinfunction "1_1") (pintype "passive"))
      (node (ref "C14") (pin "2") (pinfunction "2_2") (pintype "passive"))
      (node (ref "C16") (pin "2") (pinfunction "2_2") (pintype "passive"))
      (node (ref "C17") (pin "1") (pinfunction "1_1") (pintype "passive"))
      (node (ref "C19") (pin "1") (pinfunction "1_1") (pintype "passive"))
      (node (ref "C2") (pin "2") (pinfunction "2_2") (pintype "passive"))
      (node (ref "C21") (pin "1") (pinfunction "1_1") (pintype "passive"))
      (node (ref "C22") (pin "1") (pinfunction "1_1") (pintype "passive"))
      (node (ref "C23") (pin "2") (pinfunction "2_2") (pintype "passive"))
      (node (ref "C24") (pin "2") (pinfunction "2_2") (pintype "passive"))
      (node (ref "C25") (pin "1") (pinfunction "1_1") (pintype "passive"))
      (node (ref "C26") (pin "1") (pinfunction "1_1") (pintype "passive"))
      (node (ref "C27") (pin "1") (pinfunction "1_1") (pintype "passive"))
      (node (ref "C28") (pin "2") (pinfunction "2_2") (pintype "passive"))
      (node (ref "C29") (pin "1") (pinfunction "1_1") (pintype "passive"))
      (node (ref "C3") (pin "1") (pinfunction "1_1") (pintype "passive"))
      (node (ref "C30") (pin "1") (pinfunction "1_1") (pintype "passive"))
      (node (ref "C31") (pin "2") (pinfunction "2_2") (pintype "passive"))
      (node (ref "C32") (pin "2") (pinfunction "2_2") (pintype "passive"))
      (node (ref "C33") (pin "2") (pinfunction "2_2") (pintype "passive"))
      (node (ref "C34") (pin "1") (pinfunction "1_1") (pintype "passive"))
      (node (ref "C35") (pin "1") (pinfunction "1_1") (pintype "passive"))
      (node (ref "C36") (pin "2") (pinfunction "2_2") (pintype "passive"))
      (node (ref "C37") (pin "2") (pinfunction "2_2") (pintype "passive"))
      (node (ref "C38") (pin "2") (pinfunction "2_2") (pintype "passive"))
      (node (ref "C4") (pin "1") (pinfunction "1_1") (pintype "passive"))
      (node (ref "C5") (pin "1") (pinfunction "1_1") (pintype "passive"))
      (node (ref "C6") (pin "2") (pinfunction "2_2") (pintype "passive"))
      (node (ref "C7") (pin "2") (pinfunction "2_2") (pintype "passive"))
      (node (ref "C8") (pin "2") (pinfunction "2_2") (pintype "passive"))
      (node (ref "C9") (pin "1") (pinfunction "1_1") (pintype "passive"))
      (node (ref "CON1") (pin "10") (pinfunction "GND_10") (pintype "passive"))
      (node (ref "CON1") (pin "5") (pinfunction "GND_5") (pintype "passive"))
      (node (ref "CON1") (pin "6") (pinfunction "GND_6") (pintype "passive"))
      (node (ref "CON1") (pin "7") (pinfunction "GND_7") (pintype "passive"))
      (node (ref "CON1") (pin "8") (pinfunction "GND_8") (pintype "passive"))
      (node (ref "CON1") (pin "9") (pinfunction "GND_9") (pintype "passive"))
      (node (ref "CON2") (pin "15") (pinfunction "15_15") (pintype "passive"))
      (node (ref "CON2") (pin "18") (pinfunction "18_18") (pintype "passive"))
      (node (ref "CON2") (pin "21") (pinfunction "21_21") (pintype "passive"))
      (node (ref "CON2") (pin "24") (pinfunction "24_24") (pintype "passive"))
      (node (ref "CON2") (pin "29") (pinfunction "29_29") (pintype "passive"))
      (node (ref "CON2") (pin "39") (pinfunction "39_39") (pintype "passive"))
      (node (ref "CON2") (pin "7") (pinfunction "7_7") (pintype "passive"))
      (node (ref "CON2") (pin "79") (pinfunction "79_79") (pintype "passive"))
      (node (ref "CON2") (pin "8") (pinfunction "8_8") (pintype "passive"))
      (node (ref "CON2") (pin "80") (pinfunction "80_80") (pintype "passive"))
      (node (ref "CON3") (pin "11") (pinfunction "11_11") (pintype "passive"))
      (node (ref "CON3") (pin "12") (pinfunction "12_12") (pintype "passive"))
      (node (ref "CON3") (pin "17") (pinfunction "17_17") (pintype "passive"))
      (node (ref "CON3") (pin "18") (pinfunction "18_18") (pintype "passive"))
      (node (ref "CON3") (pin "25") (pinfunction "25_25") (pintype "passive"))
      (node (ref "CON3") (pin "26") (pinfunction "26_26") (pintype "passive"))
      (node (ref "CON3") (pin "47") (pinfunction "47_47") (pintype "passive"))
      (node (ref "CON3") (pin "57") (pinfunction "57_57") (pintype "passive"))
      (node (ref "CON3") (pin "6") (pinfunction "6_6") (pintype "passive"))
      (node (ref "CON3") (pin "60") (pinfunction "60_60") (pintype "passive"))
      (node (ref "CON3") (pin "63") (pinfunction "63_63") (pintype "passive"))
      (node (ref "CON3") (pin "66") (pinfunction "66_66") (pintype "passive"))
      (node (ref "CON3") (pin "69") (pinfunction "69_69") (pintype "passive"))
      (node (ref "CON3") (pin "78") (pinfunction "78_78") (pintype "passive"))
      (node (ref "CON4") (pin "5") (pinfunction "5_5") (pintype "passive"))
      (node (ref "CON5") (pin "11") (pinfunction "11_11") (pintype "passive"))
      (node (ref "CON5") (pin "20") (pinfunction "20_20") (pintype "passive"))
      (node (ref "CON5") (pin "27") (pinfunction "27_27") (pintype "passive"))
      (node (ref "CON5") (pin "29") (pinfunction "29_29") (pintype "passive"))
      (node (ref "CON5") (pin "32") (pinfunction "32_32") (pintype "passive"))
      (node (ref "CON5") (pin "38") (pinfunction "38_38") (pintype "passive"))
      (node (ref "CON5") (pin "39") (pinfunction "39_39") (pintype "passive"))
      (node (ref "CON5") (pin "40") (pinfunction "40_40") (pintype "passive"))
      (node (ref "CON5") (pin "41") (pinfunction "41_41") (pintype "passive"))
      (node (ref "CON5") (pin "42") (pinfunction "42_42") (pintype "passive"))
      (node (ref "CON5") (pin "6") (pinfunction "6_6") (pintype "passive"))
      (node (ref "CON6") (pin "2") (pinfunction "2_2") (pintype "passive"))
      (node (ref "CON6") (pin "21") (pinfunction "21_21") (pintype "passive"))
      (node (ref "CON6") (pin "23") (pinfunction "23_23") (pintype "passive"))
      (node (ref "CON6") (pin "24") (pinfunction "24_24") (pintype "passive"))
      (node (ref "CON7") (pin "14") (pinfunction "14_14") (pintype "passive"))
      (node (ref "CON7") (pin "15") (pinfunction "15_15") (pintype "passive"))
      (node (ref "CON7") (pin "16") (pinfunction "16_16") (pintype "passive"))
      (node (ref "CON7") (pin "17") (pinfunction "17_17") (pintype "passive"))
      (node (ref "CON7") (pin "47") (pinfunction "47_47") (pintype "passive"))
      (node (ref "CON7") (pin "74") (pinfunction "74_74") (pintype "passive"))
      (node (ref "CON7") (pin "77") (pinfunction "77_77") (pintype "passive"))
      (node (ref "CON7") (pin "78") (pinfunction "78_78") (pintype "passive"))
      (node (ref "CON7") (pin "79") (pinfunction "79_79") (pintype "passive"))
      (node (ref "CON7") (pin "80") (pinfunction "80_80") (pintype "passive"))
      (node (ref "CON8") (pin "23") (pinfunction "23_23") (pintype "passive"))
      (node (ref "CON8") (pin "25") (pinfunction "25_25") (pintype "passive"))
      (node (ref "CON8") (pin "3") (pinfunction "3_3") (pintype "passive"))
      (node (ref "CON8") (pin "4") (pinfunction "4_4") (pintype "passive"))
      (node (ref "CON8") (pin "53") (pinfunction "53_53") (pintype "passive"))
      (node (ref "CON8") (pin "63") (pinfunction "63_63") (pintype "passive"))
      (node (ref "CON8") (pin "66") (pinfunction "66_66") (pintype "passive"))
      (node (ref "CON8") (pin "75") (pinfunction "75_75") (pintype "passive"))
      (node (ref "CON8") (pin "76") (pinfunction "76_76") (pintype "passive"))
      (node (ref "CON8") (pin "77") (pinfunction "77_77") (pintype "passive"))
      (node (ref "CON8") (pin "78") (pinfunction "78_78") (pintype "passive"))
      (node (ref "CON8") (pin "79") (pinfunction "79_79") (pintype "passive"))
      (node (ref "CON8") (pin "80") (pinfunction "80_80") (pintype "passive"))
      (node (ref "J1") (pin "2") (pinfunction "2_2") (pintype "power_in"))
      (node (ref "J1") (pin "3") (pinfunction "3_3") (pintype "power_in"))
      (node (ref "K1") (pin "2") (pinfunction "2_2") (pintype "passive"))
      (node (ref "K2") (pin "2") (pinfunction "2_2") (pintype "passive"))
      (node (ref "K3") (pin "2") (pinfunction "2_2") (pintype "passive"))
      (node (ref "Q2") (pin "2") (pinfunction "E_2") (pintype "passive"))
      (node (ref "R10") (pin "2") (pinfunction "2_2") (pintype "passive"))
      (node (ref "R19") (pin "1") (pinfunction "1_1") (pintype "passive"))
      (node (ref "R2") (pin "2") (pinfunction "2_2") (pintype "passive"))
      (node (ref "R3") (pin "2") (pinfunction "2_2") (pintype "passive"))
      (node (ref "R6") (pin "2") (pinfunction "2_2") (pintype "passive"))
      (node (ref "R7") (pin "1") (pinfunction "1_1") (pintype "passive"))
      (node (ref "R9") (pin "2") (pinfunction "2_2") (pintype "passive"))
      (node (ref "U1") (pin "9") (pinfunction "GND_9") (pintype "passive"))
      (node (ref "U2") (pin "9") (pinfunction "GND_9") (pintype "passive"))
      (node (ref "U3") (pin "2") (pinfunction "GND_2") (pintype "passive"))
      (node (ref "U4") (pin "15") (pinfunction "GND_15") (pintype "passive"))
      (node (ref "U5") (pin "11") (pinfunction "GND_11") (pintype "passive"))
      (node (ref "U6") (pin "11") (pinfunction "GND_11") (pintype "passive"))
      (node (ref "U7") (pin "2") (pinfunction "GND_2") (pintype "passive"))
    )
    (net (code "77") (name "Net-(C1-Pad1)") (class "Default")
      (node (ref "C1") (pin "1") (pinfunction "1_1") (pintype "passive"))
      (node (ref "R1") (pin "1") (pinfunction "1_1") (pintype "passive"))
    )
    (net (code "78") (name "Net-(C7-Pad1)") (class "Default")
      (node (ref "C7") (pin "1") (pinfunction "1_1") (pintype "passive"))
      (node (ref "R8") (pin "1") (pinfunction "1_1") (pintype "passive"))
    )
    (net (code "79") (name "Net-(Q1-G)") (class "Default")
      (node (ref "Q1") (pin "1") (pinfunction "G_1") (pintype "passive"))
      (node (ref "R13") (pin "1") (pinfunction "1_1") (pintype "passive"))
      (node (ref "R14") (pin "2") (pinfunction "2_2") (pintype "passive"))
    )
    (net (code "80") (name "Net-(Q2-B)") (class "Default")
      (node (ref "Q2") (pin "1") (pinfunction "B_1") (pintype "passive"))
      (node (ref "R15") (pin "2") (pinfunction "2_2") (pintype "passive"))
    )
    (net (code "81") (name "Net-(Q2-C)") (class "Default")
      (node (ref "Q2") (pin "3") (pinfunction "C_3") (pintype "passive"))
      (node (ref "R14") (pin "1") (pinfunction "1_1") (pintype "passive"))
    )
    (net (code "82") (name "Net-(U1-COMP)") (class "Default")
      (node (ref "R1") (pin "2") (pinfunction "2_2") (pintype "passive"))
      (node (ref "U1") (pin "1") (pinfunction "COMP_1") (pintype "passive"))
    )
    (net (code "83") (name "Net-(U1-FB)") (class "Default")
      (node (ref "R2") (pin "1") (pinfunction "1_1") (pintype "passive"))
      (node (ref "R4") (pin "2") (pinfunction "2_2") (pintype "passive"))
      (node (ref "U1") (pin "7") (pinfunction "FB_7") (pintype "passive"))
    )
    (net (code "84") (name "Net-(U1-LX)") (class "Default")
      (node (ref "L1") (pin "1") (pinfunction "1_1") (pintype "passive"))
      (node (ref "U1") (pin "5") (pinfunction "LX_5") (pintype "passive"))
    )
    (net (code "85") (name "Net-(U1-RT)") (class "Default")
      (node (ref "R3") (pin "1") (pinfunction "1_1") (pintype "passive"))
      (node (ref "U1") (pin "6") (pinfunction "RT_6") (pintype "passive"))
    )
    (net (code "86") (name "Net-(U1-SS)") (class "Default")
      (node (ref "C2") (pin "1") (pinfunction "1_1") (pintype "passive"))
      (node (ref "U1") (pin "2") (pinfunction "SS_2") (pintype "passive"))
    )
    (net (code "87") (name "Net-(U2-COMP)") (class "Default")
      (node (ref "R8") (pin "2") (pinfunction "2_2") (pintype "passive"))
      (node (ref "U2") (pin "1") (pinfunction "COMP_1") (pintype "passive"))
    )
    (net (code "88") (name "Net-(U2-FB)") (class "Default")
      (node (ref "R11") (pin "2") (pinfunction "2_2") (pintype "passive"))
      (node (ref "R9") (pin "1") (pinfunction "1_1") (pintype "passive"))
      (node (ref "U2") (pin "7") (pinfunction "FB_7") (pintype "passive"))
    )
    (net (code "89") (name "Net-(U2-LX)") (class "Default")
      (node (ref "L2") (pin "1") (pinfunction "1_1") (pintype "passive"))
      (node (ref "U2") (pin "5") (pinfunction "LX_5") (pintype "passive"))
    )
    (net (code "90") (name "Net-(U2-RT)") (class "Default")
      (node (ref "R10") (pin "1") (pinfunction "1_1") (pintype "passive"))
      (node (ref "U2") (pin "6") (pinfunction "RT_6") (pintype "passive"))
    )
    (net (code "91") (name "Net-(U2-SS)") (class "Default")
      (node (ref "C8") (pin "1") (pinfunction "1_1") (pintype "passive"))
      (node (ref "U2") (pin "2") (pinfunction "SS_2") (pintype "passive"))
    )
    (net (code "92") (name "Net-(U4-C1+)") (class "Default")
      (node (ref "C15") (pin "2") (pinfunction "2_2") (pintype "passive"))
      (node (ref "U4") (pin "1") (pinfunction "C1+_1") (pintype "passive"))
    )
    (net (code "93") (name "Net-(U4-C1-)") (class "Default")
      (node (ref "C15") (pin "1") (pinfunction "1_1") (pintype "passive"))
      (node (ref "U4") (pin "3") (pinfunction "C1-_3") (pintype "passive"))
    )
    (net (code "94") (name "Net-(U4-C2+)") (class "Default")
      (node (ref "C20") (pin "1") (pinfunction "1_1") (pintype "passive"))
      (node (ref "U4") (pin "4") (pinfunction "C2+_4") (pintype "passive"))
    )
    (net (code "95") (name "Net-(U4-C2-)") (class "Default")
      (node (ref "C20") (pin "2") (pinfunction "2_2") (pintype "passive"))
      (node (ref "U4") (pin "5") (pinfunction "C2-_5") (pintype "passive"))
    )
    (net (code "96") (name "Net-(U4-R1IN)") (class "Default")
      (node (ref "CON4") (pin "3") (pinfunction "3_3") (pintype "passive"))
      (node (ref "U4") (pin "13") (pinfunction "R1IN_13") (pintype "passive"))
    )
    (net (code "97") (name "Net-(U4-T1OUT)") (class "Default")
      (node (ref "CON4") (pin "2") (pinfunction "2_2") (pintype "passive"))
      (node (ref "U4") (pin "14") (pinfunction "T1OUT_14") (pintype "passive"))
    )
    (net (code "98") (name "Net-(U4-V+)") (class "Default")
      (node (ref "C18") (pin "2") (pinfunction "2_2") (pintype "passive"))
      (node (ref "U4") (pin "2") (pinfunction "V+_2") (pintype "passive"))
    )
    (net (code "99") (name "Net-(U4-V-)") (class "Default")
      (node (ref "C21") (pin "2") (pinfunction "2_2") (pintype "passive"))
      (node (ref "U4") (pin "6") (pinfunction "V-_6") (pintype "passive"))
    )
    (net (code "100") (name "Net-(U7-A1)") (class "Default")
      (node (ref "R16") (pin "2") (pinfunction "2_2") (pintype "passive"))
      (node (ref "R17") (pin "2") (pinfunction "2_2") (pintype "passive"))
      (node (ref "R18") (pin "2") (pinfunction "2_2") (pintype "passive"))
      (node (ref "U7") (pin "5") (pinfunction "A1_5") (pintype "passive"))
    )
    (net (code "101") (name "VDD1V8_EXT") (class "Default")
      (node (ref "C19") (pin "2") (pinfunction "2_2") (pintype "passive"))
      (node (ref "C22") (pin "2") (pinfunction "2_2") (pintype "passive"))
      (node (ref "C27") (pin "2") (pinfunction "2_2") (pintype "passive"))
      (node (ref "C30") (pin "2") (pinfunction "2_2") (pintype "passive"))
      (node (ref "CON7") (pin "1") (pinfunction "1_1") (pintype "passive"))
      (node (ref "CON7") (pin "3") (pinfunction "3_3") (pintype "passive"))
      (node (ref "CON7") (pin "5") (pinfunction "5_5") (pintype "passive"))
      (node (ref "R20") (pin "1") (pinfunction "1_1") (pintype "passive"))
      (node (ref "R21") (pin "1") (pinfunction "1_1") (pintype "passive"))
      (node (ref "R22") (pin "1") (pinfunction "1_1") (pintype "passive"))
      (node (ref "S1") (pin "5") (pinfunction "B4_5") (pintype "passive"))
      (node (ref "S1") (pin "6") (pinfunction "B3_6") (pintype "passive"))
      (node (ref "S1") (pin "7") (pinfunction "B2_7") (pintype "passive"))
      (node (ref "S1") (pin "8") (pinfunction "B1_8") (pintype "passive"))
      (node (ref "U3") (pin "3") (pinfunction "VCCA_3") (pintype "passive"))
      (node (ref "U3") (pin "6") (pinfunction "OE_6") (pintype "passive"))
      (node (ref "U5") (pin "10") (pinfunction "OE_10") (pintype "passive"))
      (node (ref "U5") (pin "2") (pinfunction "VCCA_2") (pintype "passive"))
      (node (ref "U6") (pin "10") (pinfunction "OE_10") (pintype "passive"))
      (node (ref "U6") (pin "2") (pinfunction "VCCA_2") (pintype "passive"))
      (node (ref "U7") (pin "3") (pinfunction "VCCA_3") (pintype "passive"))
      (node (ref "U7") (pin "6") (pinfunction "OE_6") (pintype "passive"))
    )
    (net (code "102") (name "VDD25") (class "Default")
      (node (ref "C11") (pin "2") (pinfunction "2_2") (pintype "passive"))
      (node (ref "C23") (pin "1") (pinfunction "1_1") (pintype "passive"))
      (node (ref "C28") (pin "1") (pinfunction "1_1") (pintype "passive"))
      (node (ref "C29") (pin "2") (pinfunction "2_2") (pintype "passive"))
      (node (ref "C36") (pin "1") (pinfunction "1_1") (pintype "passive"))
      (node (ref "C37") (pin "1") (pinfunction "1_1") (pintype "passive"))
      (node (ref "C38") (pin "1") (pinfunction "1_1") (pintype "passive"))
      (node (ref "CON6") (pin "22") (pinfunction "22_22") (pintype "passive"))
      (node (ref "L2") (pin "2") (pinfunction "2_2") (pintype "passive"))
      (node (ref "R11") (pin "1") (pinfunction "1_1") (pintype "passive"))
      (node (ref "U5") (pin "19") (pinfunction "VCCB_19") (pintype "passive"))
      (node (ref "U6") (pin "19") (pinfunction "VCCB_19") (pintype "passive"))
      (node (ref "U7") (pin "7") (pinfunction "VCCB_7") (pintype "passive"))
    )
    (net (code "103") (name "VSYS") (class "Default")
      (node (ref "C10") (pin "2") (pinfunction "2_2") (pintype "passive"))
      (node (ref "C26") (pin "2") (pinfunction "2_2") (pintype "passive"))
      (node (ref "C3") (pin "2") (pinfunction "2_2") (pintype "passive"))
      (node (ref "C34") (pin "2") (pinfunction "2_2") (pintype "passive"))
      (node (ref "C35") (pin "2") (pinfunction "2_2") (pintype "passive"))
      (node (ref "C5") (pin "2") (pinfunction "2_2") (pintype "passive"))
      (node (ref "C6") (pin "1") (pinfunction "1_1") (pintype "passive"))
      (node (ref "CON6") (pin "1") (pinfunction "1_1") (pintype "passive"))
      (node (ref "CON6") (pin "11") (pinfunction "11_11") (pintype "passive"))
      (node (ref "J1") (pin "1") (pinfunction "1_1") (pintype "power_in"))
      (node (ref "Q1") (pin "2") (pinfunction "S_2") (pintype "passive"))
      (node (ref "R12") (pin "1") (pinfunction "1_1") (pintype "passive"))
      (node (ref "R13") (pin "2") (pinfunction "2_2") (pintype "passive"))
      (node (ref "R5") (pin "1") (pinfunction "1_1") (pintype "passive"))
      (node (ref "U1") (pin "3") (pinfunction "EN_3") (pintype "passive"))
      (node (ref "U1") (pin "4") (pinfunction "VIN_4") (pintype "passive"))
      (node (ref "U2") (pin "3") (pinfunction "EN_3") (pintype "passive"))
      (node (ref "U2") (pin "4") (pinfunction "VIN_4") (pintype "passive"))
    )
    (net (code "104") (name "VSYS_K") (class "Default")
      (node (ref "C12") (pin "1") (pinfunction "1_1") (pintype "passive"))
      (node (ref "C13") (pin "2") (pinfunction "2_2") (pintype "passive"))
      (node (ref "C14") (pin "1") (pinfunction "1_1") (pintype "passive"))
      (node (ref "C32") (pin "1") (pinfunction "1_1") (pintype "passive"))
      (node (ref "C33") (pin "1") (pinfunction "1_1") (pintype "passive"))
      (node (ref "C4") (pin "2") (pinfunction "2_2") (pintype "passive"))
      (node (ref "CON2") (pin "1") (pinfunction "1_1") (pintype "passive"))
      (node (ref "CON2") (pin "2") (pinfunction "2_2") (pintype "passive"))
      (node (ref "CON2") (pin "3") (pinfunction "3_3") (pintype "passive"))
      (node (ref "CON2") (pin "4") (pinfunction "4_4") (pintype "passive"))
      (node (ref "CON2") (pin "5") (pinfunction "5_5") (pintype "passive"))
      (node (ref "CON2") (pin "6") (pinfunction "6_6") (pintype "passive"))
      (node (ref "CON7") (pin "75") (pinfunction "75_75") (pintype "passive"))
      (node (ref "CON7") (pin "76") (pinfunction "76_76") (pintype "passive"))
      (node (ref "L1") (pin "2") (pinfunction "2_2") (pintype "passive"))
      (node (ref "R4") (pin "1") (pinfunction "1_1") (pintype "passive"))
    )
    (net (code "105") (name "VSYS_LCD") (class "Default")
      (node (ref "C24") (pin "1") (pinfunction "1_1") (pintype "passive"))
      (node (ref "C25") (pin "2") (pinfunction "2_2") (pintype "passive"))
      (node (ref "CON5") (pin "1") (pinfunction "1_1") (pintype "passive"))
      (node (ref "CON5") (pin "2") (pinfunction "2_2") (pintype "passive"))
      (node (ref "CON5") (pin "3") (pinfunction "3_3") (pintype "passive"))
      (node (ref "CON5") (pin "4") (pinfunction "4_4") (pintype "passive"))
      (node (ref "CON5") (pin "5") (pinfunction "5_5") (pintype "passive"))
      (node (ref "Q1") (pin "3") (pinfunction "D_3") (pintype "passive"))
      (node (ref "R12") (pin "2") (pinfunction "2_2") (pintype "passive"))
    )
    (net (code "106") (name "unconnected-(CON2-Pad9)") (class "Default")
      (node (ref "CON2") (pin "9") (pinfunction "9_9") (pintype "passive"))
    )
    (net (code "107") (name "unconnected-(CON2-Pad10)") (class "Default")
      (node (ref "CON2") (pin "10") (pinfunction "10_10") (pintype "passive"))
    )
    (net (code "108") (name "unconnected-(CON2-Pad11)") (class "Default")
      (node (ref "CON2") (pin "11") (pinfunction "11_11") (pintype "passive"))
    )
    (net (code "109") (name "unconnected-(CON2-Pad13)") (class "Default")
      (node (ref "CON2") (pin "13") (pinfunction "13_13") (pintype "passive"))
    )
    (net (code "110") (name "unconnected-(CON2-Pad17)") (class "Default")
      (node (ref "CON2") (pin "17") (pinfunction "17_17") (pintype "passive"))
    )
    (net (code "111") (name "unconnected-(CON2-Pad19)") (class "Default")
      (node (ref "CON2") (pin "19") (pinfunction "19_19") (pintype "passive"))
    )
    (net (code "112") (name "unconnected-(CON2-Pad20)") (class "Default")
      (node (ref "CON2") (pin "20") (pinfunction "20_20") (pintype "passive"))
    )
    (net (code "113") (name "unconnected-(CON2-Pad22)") (class "Default")
      (node (ref "CON2") (pin "22") (pinfunction "22_22") (pintype "passive"))
    )
    (net (code "114") (name "unconnected-(CON2-Pad23)") (class "Default")
      (node (ref "CON2") (pin "23") (pinfunction "23_23") (pintype "passive"))
    )
    (net (code "115") (name "unconnected-(CON2-Pad25)") (class "Default")
      (node (ref "CON2") (pin "25") (pinfunction "25_25") (pintype "passive"))
    )
    (net (code "116") (name "unconnected-(CON2-Pad26)") (class "Default")
      (node (ref "CON2") (pin "26") (pinfunction "26_26") (pintype "passive"))
    )
    (net (code "117") (name "unconnected-(CON2-Pad27)") (class "Default")
      (node (ref "CON2") (pin "27") (pinfunction "27_27") (pintype "passive"))
    )
    (net (code "118") (name "unconnected-(CON2-Pad28)") (class "Default")
      (node (ref "CON2") (pin "28") (pinfunction "28_28") (pintype "passive"))
    )
    (net (code "119") (name "unconnected-(CON2-Pad30)") (class "Default")
      (node (ref "CON2") (pin "30") (pinfunction "30_30") (pintype "passive"))
    )
    (net (code "120") (name "unconnected-(CON2-Pad31)") (class "Default")
      (node (ref "CON2") (pin "31") (pinfunction "31_31") (pintype "passive"))
    )
    (net (code "121") (name "unconnected-(CON2-Pad32)") (class "Default")
      (node (ref "CON2") (pin "32") (pinfunction "32_32") (pintype "passive"))
    )
    (net (code "122") (name "unconnected-(CON2-Pad33)") (class "Default")
      (node (ref "CON2") (pin "33") (pinfunction "33_33") (pintype "passive"))
    )
    (net (code "123") (name "unconnected-(CON2-Pad34)") (class "Default")
      (node (ref "CON2") (pin "34") (pinfunction "34_34") (pintype "passive"))
    )
    (net (code "124") (name "unconnected-(CON2-Pad35)") (class "Default")
      (node (ref "CON2") (pin "35") (pinfunction "35_35") (pintype "passive"))
    )
    (net (code "125") (name "unconnected-(CON2-Pad36)") (class "Default")
      (node (ref "CON2") (pin "36") (pinfunction "36_36") (pintype "passive"))
    )
    (net (code "126") (name "unconnected-(CON2-Pad37)") (class "Default")
      (node (ref "CON2") (pin "37") (pinfunction "37_37") (pintype "passive"))
    )
    (net (code "127") (name "unconnected-(CON2-Pad38)") (class "Default")
      (node (ref "CON2") (pin "38") (pinfunction "38_38") (pintype "passive"))
    )
    (net (code "128") (name "unconnected-(CON2-Pad40)") (class "Default")
      (node (ref "CON2") (pin "40") (pinfunction "40_40") (pintype "passive"))
    )
    (net (code "129") (name "unconnected-(CON2-Pad41)") (class "Default")
      (node (ref "CON2") (pin "41") (pinfunction "41_41") (pintype "passive"))
    )
    (net (code "130") (name "unconnected-(CON2-Pad42)") (class "Default")
      (node (ref "CON2") (pin "42") (pinfunction "42_42") (pintype "passive"))
    )
    (net (code "131") (name "unconnected-(CON2-Pad43)") (class "Default")
      (node (ref "CON2") (pin "43") (pinfunction "43_43") (pintype "passive"))
    )
    (net (code "132") (name "unconnected-(CON2-Pad44)") (class "Default")
      (node (ref "CON2") (pin "44") (pinfunction "44_44") (pintype "passive"))
    )
    (net (code "133") (name "unconnected-(CON2-Pad45)") (class "Default")
      (node (ref "CON2") (pin "45") (pinfunction "45_45") (pintype "passive"))
    )
    (net (code "134") (name "unconnected-(CON2-Pad46)") (class "Default")
      (node (ref "CON2") (pin "46") (pinfunction "46_46") (pintype "passive"))
    )
    (net (code "135") (name "unconnected-(CON2-Pad47)") (class "Default")
      (node (ref "CON2") (pin "47") (pinfunction "47_47") (pintype "passive"))
    )
    (net (code "136") (name "unconnected-(CON2-Pad48)") (class "Default")
      (node (ref "CON2") (pin "48") (pinfunction "48_48") (pintype "passive"))
    )
    (net (code "137") (name "unconnected-(CON2-Pad49)") (class "Default")
      (node (ref "CON2") (pin "49") (pinfunction "49_49") (pintype "passive"))
    )
    (net (code "138") (name "unconnected-(CON2-Pad50)") (class "Default")
      (node (ref "CON2") (pin "50") (pinfunction "50_50") (pintype "passive"))
    )
    (net (code "139") (name "unconnected-(CON2-Pad51)") (class "Default")
      (node (ref "CON2") (pin "51") (pinfunction "51_51") (pintype "passive"))
    )
    (net (code "140") (name "unconnected-(CON2-Pad52)") (class "Default")
      (node (ref "CON2") (pin "52") (pinfunction "52_52") (pintype "passive"))
    )
    (net (code "141") (name "unconnected-(CON2-Pad53)") (class "Default")
      (node (ref "CON2") (pin "53") (pinfunction "53_53") (pintype "passive"))
    )
    (net (code "142") (name "unconnected-(CON2-Pad56)") (class "Default")
      (node (ref "CON2") (pin "56") (pinfunction "56_56") (pintype "passive"))
    )
    (net (code "143") (name "unconnected-(CON2-Pad57)") (class "Default")
      (node (ref "CON2") (pin "57") (pinfunction "57_57") (pintype "passive"))
    )
    (net (code "144") (name "unconnected-(CON2-Pad58)") (class "Default")
      (node (ref "CON2") (pin "58") (pinfunction "58_58") (pintype "passive"))
    )
    (net (code "145") (name "unconnected-(CON2-Pad59)") (class "Default")
      (node (ref "CON2") (pin "59") (pinfunction "59_59") (pintype "passive"))
    )
    (net (code "146") (name "unconnected-(CON2-Pad60)") (class "Default")
      (node (ref "CON2") (pin "60") (pinfunction "60_60") (pintype "passive"))
    )
    (net (code "147") (name "unconnected-(CON2-Pad61)") (class "Default")
      (node (ref "CON2") (pin "61") (pinfunction "61_61") (pintype "passive"))
    )
    (net (code "148") (name "unconnected-(CON2-Pad62)") (class "Default")
      (node (ref "CON2") (pin "62") (pinfunction "62_62") (pintype "passive"))
    )
    (net (code "149") (name "unconnected-(CON2-Pad63)") (class "Default")
      (node (ref "CON2") (pin "63") (pinfunction "63_63") (pintype "passive"))
    )
    (net (code "150") (name "unconnected-(CON2-Pad64)") (class "Default")
      (node (ref "CON2") (pin "64") (pinfunction "64_64") (pintype "passive"))
    )
    (net (code "151") (name "unconnected-(CON2-Pad66)") (class "Default")
      (node (ref "CON2") (pin "66") (pinfunction "66_66") (pintype "passive"))
    )
    (net (code "152") (name "unconnected-(CON2-Pad68)") (class "Default")
      (node (ref "CON2") (pin "68") (pinfunction "68_68") (pintype "passive"))
    )
    (net (code "153") (name "unconnected-(CON2-Pad69)") (class "Default")
      (node (ref "CON2") (pin "69") (pinfunction "69_69") (pintype "passive"))
    )
    (net (code "154") (name "unconnected-(CON2-Pad70)") (class "Default")
      (node (ref "CON2") (pin "70") (pinfunction "70_70") (pintype "passive"))
    )
    (net (code "155") (name "unconnected-(CON2-Pad71)") (class "Default")
      (node (ref "CON2") (pin "71") (pinfunction "71_71") (pintype "passive"))
    )
    (net (code "156") (name "unconnected-(CON2-Pad72)") (class "Default")
      (node (ref "CON2") (pin "72") (pinfunction "72_72") (pintype "passive"))
    )
    (net (code "157") (name "unconnected-(CON2-Pad73)") (class "Default")
      (node (ref "CON2") (pin "73") (pinfunction "73_73") (pintype "passive"))
    )
    (net (code "158") (name "unconnected-(CON2-Pad74)") (class "Default")
      (node (ref "CON2") (pin "74") (pinfunction "74_74") (pintype "passive"))
    )
    (net (code "159") (name "unconnected-(CON2-Pad75)") (class "Default")
      (node (ref "CON2") (pin "75") (pinfunction "75_75") (pintype "passive"))
    )
    (net (code "160") (name "unconnected-(CON2-Pad76)") (class "Default")
      (node (ref "CON2") (pin "76") (pinfunction "76_76") (pintype "passive"))
    )
    (net (code "161") (name "unconnected-(CON2-Pad77)") (class "Default")
      (node (ref "CON2") (pin "77") (pinfunction "77_77") (pintype "passive"))
    )
    (net (code "162") (name "unconnected-(CON2-Pad78)") (class "Default")
      (node (ref "CON2") (pin "78") (pinfunction "78_78") (pintype "passive"))
    )
    (net (code "163") (name "unconnected-(CON3-Pad1)") (class "Default")
      (node (ref "CON3") (pin "1") (pinfunction "1_1") (pintype "passive"))
    )
    (net (code "164") (name "unconnected-(CON3-Pad2)") (class "Default")
      (node (ref "CON3") (pin "2") (pinfunction "2_2") (pintype "passive"))
    )
    (net (code "165") (name "unconnected-(CON3-Pad3)") (class "Default")
      (node (ref "CON3") (pin "3") (pinfunction "3_3") (pintype "passive"))
    )
    (net (code "166") (name "unconnected-(CON3-Pad4)") (class "Default")
      (node (ref "CON3") (pin "4") (pinfunction "4_4") (pintype "passive"))
    )
    (net (code "167") (name "unconnected-(CON3-Pad5)") (class "Default")
      (node (ref "CON3") (pin "5") (pinfunction "5_5") (pintype "passive"))
    )
    (net (code "168") (name "unconnected-(CON3-Pad7)") (class "Default")
      (node (ref "CON3") (pin "7") (pinfunction "7_7") (pintype "passive"))
    )
    (net (code "169") (name "unconnected-(CON3-Pad8)") (class "Default")
      (node (ref "CON3") (pin "8") (pinfunction "8_8") (pintype "passive"))
    )
    (net (code "170") (name "unconnected-(CON3-Pad9)") (class "Default")
      (node (ref "CON3") (pin "9") (pinfunction "9_9") (pintype "passive"))
    )
    (net (code "171") (name "unconnected-(CON3-Pad10)") (class "Default")
      (node (ref "CON3") (pin "10") (pinfunction "10_10") (pintype "passive"))
    )
    (net (code "172") (name "unconnected-(CON3-Pad13)") (class "Default")
      (node (ref "CON3") (pin "13") (pinfunction "13_13") (pintype "passive"))
    )
    (net (code "173") (name "unconnected-(CON3-Pad14)") (class "Default")
      (node (ref "CON3") (pin "14") (pinfunction "14_14") (pintype "passive"))
    )
    (net (code "174") (name "unconnected-(CON3-Pad15)") (class "Default")
      (node (ref "CON3") (pin "15") (pinfunction "15_15") (pintype "passive"))
    )
    (net (code "175") (name "unconnected-(CON3-Pad16)") (class "Default")
      (node (ref "CON3") (pin "16") (pinfunction "16_16") (pintype "passive"))
    )
    (net (code "176") (name "unconnected-(CON3-Pad19)") (class "Default")
      (node (ref "CON3") (pin "19") (pinfunction "19_19") (pintype "passive"))
    )
    (net (code "177") (name "unconnected-(CON3-Pad20)") (class "Default")
      (node (ref "CON3") (pin "20") (pinfunction "20_20") (pintype "passive"))
    )
    (net (code "178") (name "unconnected-(CON3-Pad21)") (class "Default")
      (node (ref "CON3") (pin "21") (pinfunction "21_21") (pintype "passive"))
    )
    (net (code "179") (name "unconnected-(CON3-Pad22)") (class "Default")
      (node (ref "CON3") (pin "22") (pinfunction "22_22") (pintype "passive"))
    )
    (net (code "180") (name "unconnected-(CON3-Pad23)") (class "Default")
      (node (ref "CON3") (pin "23") (pinfunction "23_23") (pintype "passive"))
    )
    (net (code "181") (name "unconnected-(CON3-Pad27)") (class "Default")
      (node (ref "CON3") (pin "27") (pinfunction "27_27") (pintype "passive"))
    )
    (net (code "182") (name "unconnected-(CON3-Pad28)") (class "Default")
      (node (ref "CON3") (pin "28") (pinfunction "28_28") (pintype "passive"))
    )
    (net (code "183") (name "unconnected-(CON3-Pad29)") (class "Default")
      (node (ref "CON3") (pin "29") (pinfunction "29_29") (pintype "passive"))
    )
    (net (code "184") (name "unconnected-(CON3-Pad30)") (class "Default")
      (node (ref "CON3") (pin "30") (pinfunction "30_30") (pintype "passive"))
    )
    (net (code "185") (name "unconnected-(CON3-Pad31)") (class "Default")
      (node (ref "CON3") (pin "31") (pinfunction "31_31") (pintype "passive"))
    )
    (net (code "186") (name "unconnected-(CON3-Pad32)") (class "Default")
      (node (ref "CON3") (pin "32") (pinfunction "32_32") (pintype "passive"))
    )
    (net (code "187") (name "unconnected-(CON3-Pad33)") (class "Default")
      (node (ref "CON3") (pin "33") (pinfunction "33_33") (pintype "passive"))
    )
    (net (code "188") (name "unconnected-(CON3-Pad34)") (class "Default")
      (node (ref "CON3") (pin "34") (pinfunction "34_34") (pintype "passive"))
    )
    (net (code "189") (name "unconnected-(CON3-Pad35)") (class "Default")
      (node (ref "CON3") (pin "35") (pinfunction "35_35") (pintype "passive"))
    )
    (net (code "190") (name "unconnected-(CON3-Pad36)") (class "Default")
      (node (ref "CON3") (pin "36") (pinfunction "36_36") (pintype "passive"))
    )
    (net (code "191") (name "unconnected-(CON3-Pad39)") (class "Default")
      (node (ref "CON3") (pin "39") (pinfunction "39_39") (pintype "passive"))
    )
    (net (code "192") (name "unconnected-(CON3-Pad40)") (class "Default")
      (node (ref "CON3") (pin "40") (pinfunction "40_40") (pintype "passive"))
    )
    (net (code "193") (name "unconnected-(CON3-Pad42)") (class "Default")
      (node (ref "CON3") (pin "42") (pinfunction "42_42") (pintype "passive"))
    )
    (net (code "194") (name "unconnected-(CON3-Pad44)") (class "Default")
      (node (ref "CON3") (pin "44") (pinfunction "44_44") (pintype "passive"))
    )
    (net (code "195") (name "unconnected-(CON3-Pad46)") (class "Default")
      (node (ref "CON3") (pin "46") (pinfunction "46_46") (pintype "passive"))
    )
    (net (code "196") (name "unconnected-(CON3-Pad48)") (class "Default")
      (node (ref "CON3") (pin "48") (pinfunction "48_48") (pintype "passive"))
    )
    (net (code "197") (name "unconnected-(CON3-Pad49)") (class "Default")
      (node (ref "CON3") (pin "49") (pinfunction "49_49") (pintype "passive"))
    )
    (net (code "198") (name "unconnected-(CON3-Pad50)") (class "Default")
      (node (ref "CON3") (pin "50") (pinfunction "50_50") (pintype "passive"))
    )
    (net (code "199") (name "unconnected-(CON3-Pad51)") (class "Default")
      (node (ref "CON3") (pin "51") (pinfunction "51_51") (pintype "passive"))
    )
    (net (code "200") (name "unconnected-(CON3-Pad53)") (class "Default")
      (node (ref "CON3") (pin "53") (pinfunction "53_53") (pintype "passive"))
    )
    (net (code "201") (name "unconnected-(CON3-Pad54)") (class "Default")
      (node (ref "CON3") (pin "54") (pinfunction "54_54") (pintype "passive"))
    )
    (net (code "202") (name "unconnected-(CON3-Pad55)") (class "Default")
      (node (ref "CON3") (pin "55") (pinfunction "55_55") (pintype "passive"))
    )
    (net (code "203") (name "unconnected-(CON3-Pad56)") (class "Default")
      (node (ref "CON3") (pin "56") (pinfunction "56_56") (pintype "passive"))
    )
    (net (code "204") (name "unconnected-(CON3-Pad58)") (class "Default")
      (node (ref "CON3") (pin "58") (pinfunction "58_58") (pintype "passive"))
    )
    (net (code "205") (name "unconnected-(CON3-Pad59)") (class "Default")
      (node (ref "CON3") (pin "59") (pinfunction "59_59") (pintype "passive"))
    )
    (net (code "206") (name "unconnected-(CON3-Pad61)") (class "Default")
      (node (ref "CON3") (pin "61") (pinfunction "61_61") (pintype "passive"))
    )
    (net (code "207") (name "unconnected-(CON3-Pad62)") (class "Default")
      (node (ref "CON3") (pin "62") (pinfunction "62_62") (pintype "passive"))
    )
    (net (code "208") (name "unconnected-(CON3-Pad64)") (class "Default")
      (node (ref "CON3") (pin "64") (pinfunction "64_64") (pintype "passive"))
    )
    (net (code "209") (name "unconnected-(CON3-Pad65)") (class "Default")
      (node (ref "CON3") (pin "65") (pinfunction "65_65") (pintype "passive"))
    )
    (net (code "210") (name "unconnected-(CON3-Pad67)") (class "Default")
      (node (ref "CON3") (pin "67") (pinfunction "67_67") (pintype "passive"))
    )
    (net (code "211") (name "unconnected-(CON3-Pad68)") (class "Default")
      (node (ref "CON3") (pin "68") (pinfunction "68_68") (pintype "passive"))
    )
    (net (code "212") (name "unconnected-(CON3-Pad70)") (class "Default")
      (node (ref "CON3") (pin "70") (pinfunction "70_70") (pintype "passive"))
    )
    (net (code "213") (name "unconnected-(CON3-Pad71)") (class "Default")
      (node (ref "CON3") (pin "71") (pinfunction "71_71") (pintype "passive"))
    )
    (net (code "214") (name "unconnected-(CON3-Pad72)") (class "Default")
      (node (ref "CON3") (pin "72") (pinfunction "72_72") (pintype "passive"))
    )
    (net (code "215") (name "unconnected-(CON3-Pad73)") (class "Default")
      (node (ref "CON3") (pin "73") (pinfunction "73_73") (pintype "passive"))
    )
    (net (code "216") (name "unconnected-(CON3-Pad74)") (class "Default")
      (node (ref "CON3") (pin "74") (pinfunction "74_74") (pintype "passive"))
    )
    (net (code "217") (name "unconnected-(CON3-Pad75)") (class "Default")
      (node (ref "CON3") (pin "75") (pinfunction "75_75") (pintype "passive"))
    )
    (net (code "218") (name "unconnected-(CON3-Pad76)") (class "Default")
      (node (ref "CON3") (pin "76") (pinfunction "76_76") (pintype "passive"))
    )
    (net (code "219") (name "unconnected-(CON3-Pad77)") (class "Default")
      (node (ref "CON3") (pin "77") (pinfunction "77_77") (pintype "passive"))
    )
    (net (code "220") (name "unconnected-(CON3-Pad79)") (class "Default")
      (node (ref "CON3") (pin "79") (pinfunction "79_79") (pintype "passive"))
    )
    (net (code "221") (name "unconnected-(CON3-Pad80)") (class "Default")
      (node (ref "CON3") (pin "80") (pinfunction "80_80") (pintype "passive"))
    )
    (net (code "222") (name "unconnected-(CON4-MH1-Pad10)") (class "Default")
      (node (ref "CON4") (pin "10") (pinfunction "MH1_10") (pintype "passive"))
    )
    (net (code "223") (name "unconnected-(CON4-MH2-Pad11)") (class "Default")
      (node (ref "CON4") (pin "11") (pinfunction "MH2_11") (pintype "passive"))
    )
    (net (code "224") (name "unconnected-(CON4-Pad1)") (class "Default")
      (node (ref "CON4") (pin "1") (pinfunction "1_1") (pintype "passive"))
    )
    (net (code "225") (name "unconnected-(CON4-Pad4)") (class "Default")
      (node (ref "CON4") (pin "4") (pinfunction "4_4") (pintype "passive"))
    )
    (net (code "226") (name "unconnected-(CON4-Pad6)") (class "Default")
      (node (ref "CON4") (pin "6") (pinfunction "6_6") (pintype "passive"))
    )
    (net (code "227") (name "unconnected-(CON4-Pad7)") (class "Default")
      (node (ref "CON4") (pin "7") (pinfunction "7_7") (pintype "passive"))
    )
    (net (code "228") (name "unconnected-(CON4-Pad8)") (class "Default")
      (node (ref "CON4") (pin "8") (pinfunction "8_8") (pintype "passive"))
    )
    (net (code "229") (name "unconnected-(CON4-Pad9)") (class "Default")
      (node (ref "CON4") (pin "9") (pinfunction "9_9") (pintype "passive"))
    )
    (net (code "230") (name "unconnected-(CON7-Pad2)") (class "Default")
      (node (ref "CON7") (pin "2") (pinfunction "2_2") (pintype "passive"))
    )
    (net (code "231") (name "unconnected-(CON7-Pad4)") (class "Default")
      (node (ref "CON7") (pin "4") (pinfunction "4_4") (pintype "passive"))
    )
    (net (code "232") (name "unconnected-(CON7-Pad6)") (class "Default")
      (node (ref "CON7") (pin "6") (pinfunction "6_6") (pintype "passive"))
    )
    (net (code "233") (name "unconnected-(CON7-Pad7)") (class "Default")
      (node (ref "CON7") (pin "7") (pinfunction "7_7") (pintype "passive"))
    )
    (net (code "234") (name "unconnected-(CON7-Pad8)") (class "Default")
      (node (ref "CON7") (pin "8") (pinfunction "8_8") (pintype "passive"))
    )
    (net (code "235") (name "unconnected-(CON7-Pad9)") (class "Default")
      (node (ref "CON7") (pin "9") (pinfunction "9_9") (pintype "passive"))
    )
    (net (code "236") (name "unconnected-(CON7-Pad10)") (class "Default")
      (node (ref "CON7") (pin "10") (pinfunction "10_10") (pintype "passive"))
    )
    (net (code "237") (name "unconnected-(CON7-Pad11)") (class "Default")
      (node (ref "CON7") (pin "11") (pinfunction "11_11") (pintype "passive"))
    )
    (net (code "238") (name "unconnected-(CON7-Pad12)") (class "Default")
      (node (ref "CON7") (pin "12") (pinfunction "12_12") (pintype "passive"))
    )
    (net (code "239") (name "unconnected-(CON7-Pad13)") (class "Default")
      (node (ref "CON7") (pin "13") (pinfunction "13_13") (pintype "passive"))
    )
    (net (code "240") (name "unconnected-(CON7-Pad46)") (class "Default")
      (node (ref "CON7") (pin "46") (pinfunction "46_46") (pintype "passive"))
    )
    (net (code "241") (name "unconnected-(CON7-Pad48)") (class "Default")
      (node (ref "CON7") (pin "48") (pinfunction "48_48") (pintype "passive"))
    )
    (net (code "242") (name "unconnected-(CON7-Pad49)") (class "Default")
      (node (ref "CON7") (pin "49") (pinfunction "49_49") (pintype "passive"))
    )
    (net (code "243") (name "unconnected-(CON7-Pad50)") (class "Default")
      (node (ref "CON7") (pin "50") (pinfunction "50_50") (pintype "passive"))
    )
    (net (code "244") (name "unconnected-(CON7-Pad51)") (class "Default")
      (node (ref "CON7") (pin "51") (pinfunction "51_51") (pintype "passive"))
    )
    (net (code "245") (name "unconnected-(CON7-Pad53)") (class "Default")
      (node (ref "CON7") (pin "53") (pinfunction "53_53") (pintype "passive"))
    )
    (net (code "246") (name "unconnected-(CON7-Pad55)") (class "Default")
      (node (ref "CON7") (pin "55") (pinfunction "55_55") (pintype "passive"))
    )
    (net (code "247") (name "unconnected-(CON7-Pad57)") (class "Default")
      (node (ref "CON7") (pin "57") (pinfunction "57_57") (pintype "passive"))
    )
    (net (code "248") (name "unconnected-(CON7-Pad59)") (class "Default")
      (node (ref "CON7") (pin "59") (pinfunction "59_59") (pintype "passive"))
    )
    (net (code "249") (name "unconnected-(CON7-Pad60)") (class "Default")
      (node (ref "CON7") (pin "60") (pinfunction "60_60") (pintype "passive"))
    )
    (net (code "250") (name "unconnected-(CON7-Pad61)") (class "Default")
      (node (ref "CON7") (pin "61") (pinfunction "61_61") (pintype "passive"))
    )
    (net (code "251") (name "unconnected-(CON7-Pad62)") (class "Default")
      (node (ref "CON7") (pin "62") (pinfunction "62_62") (pintype "passive"))
    )
    (net (code "252") (name "unconnected-(CON7-Pad63)") (class "Default")
      (node (ref "CON7") (pin "63") (pinfunction "63_63") (pintype "passive"))
    )
    (net (code "253") (name "unconnected-(CON7-Pad64)") (class "Default")
      (node (ref "CON7") (pin "64") (pinfunction "64_64") (pintype "passive"))
    )
    (net (code "254") (name "unconnected-(CON7-Pad65)") (class "Default")
      (node (ref "CON7") (pin "65") (pinfunction "65_65") (pintype "passive"))
    )
    (net (code "255") (name "unconnected-(CON7-Pad68)") (class "Default")
      (node (ref "CON7") (pin "68") (pinfunction "68_68") (pintype "passive"))
    )
    (net (code "256") (name "unconnected-(CON7-Pad69)") (class "Default")
      (node (ref "CON7") (pin "69") (pinfunction "69_69") (pintype "passive"))
    )
    (net (code "257") (name "unconnected-(CON7-Pad71)") (class "Default")
      (node (ref "CON7") (pin "71") (pinfunction "71_71") (pintype "passive"))
    )
    (net (code "258") (name "unconnected-(CON7-Pad73)") (class "Default")
      (node (ref "CON7") (pin "73") (pinfunction "73_73") (pintype "passive"))
    )
    (net (code "259") (name "unconnected-(CON8-Pad8)") (class "Default")
      (node (ref "CON8") (pin "8") (pinfunction "8_8") (pintype "passive"))
    )
    (net (code "260") (name "unconnected-(CON8-Pad12)") (class "Default")
      (node (ref "CON8") (pin "12") (pinfunction "12_12") (pintype "passive"))
    )
    (net (code "261") (name "unconnected-(CON8-Pad13)") (class "Default")
      (node (ref "CON8") (pin "13") (pinfunction "13_13") (pintype "passive"))
    )
    (net (code "262") (name "unconnected-(CON8-Pad14)") (class "Default")
      (node (ref "CON8") (pin "14") (pinfunction "14_14") (pintype "passive"))
    )
    (net (code "263") (name "unconnected-(CON8-Pad15)") (class "Default")
      (node (ref "CON8") (pin "15") (pinfunction "15_15") (pintype "passive"))
    )
    (net (code "264") (name "unconnected-(CON8-Pad16)") (class "Default")
      (node (ref "CON8") (pin "16") (pinfunction "16_16") (pintype "passive"))
    )
    (net (code "265") (name "unconnected-(CON8-Pad17)") (class "Default")
      (node (ref "CON8") (pin "17") (pinfunction "17_17") (pintype "passive"))
    )
    (net (code "266") (name "unconnected-(CON8-Pad19)") (class "Default")
      (node (ref "CON8") (pin "19") (pinfunction "19_19") (pintype "passive"))
    )
    (net (code "267") (name "unconnected-(CON8-Pad20)") (class "Default")
      (node (ref "CON8") (pin "20") (pinfunction "20_20") (pintype "passive"))
    )
    (net (code "268") (name "unconnected-(CON8-Pad21)") (class "Default")
      (node (ref "CON8") (pin "21") (pinfunction "21_21") (pintype "passive"))
    )
    (net (code "269") (name "unconnected-(CON8-Pad22)") (class "Default")
      (node (ref "CON8") (pin "22") (pinfunction "22_22") (pintype "passive"))
    )
    (net (code "270") (name "unconnected-(CON8-Pad24)") (class "Default")
      (node (ref "CON8") (pin "24") (pinfunction "24_24") (pintype "passive"))
    )
    (net (code "271") (name "unconnected-(CON8-Pad26)") (class "Default")
      (node (ref "CON8") (pin "26") (pinfunction "26_26") (pintype "passive"))
    )
    (net (code "272") (name "unconnected-(CON8-Pad27)") (class "Default")
      (node (ref "CON8") (pin "27") (pinfunction "27_27") (pintype "passive"))
    )
    (net (code "273") (name "unconnected-(CON8-Pad28)") (class "Default")
      (node (ref "CON8") (pin "28") (pinfunction "28_28") (pintype "passive"))
    )
    (net (code "274") (name "unconnected-(CON8-Pad29)") (class "Default")
      (node (ref "CON8") (pin "29") (pinfunction "29_29") (pintype "passive"))
    )
    (net (code "275") (name "unconnected-(CON8-Pad30)") (class "Default")
      (node (ref "CON8") (pin "30") (pinfunction "30_30") (pintype "passive"))
    )
    (net (code "276") (name "unconnected-(CON8-Pad31)") (class "Default")
      (node (ref "CON8") (pin "31") (pinfunction "31_31") (pintype "passive"))
    )
    (net (code "277") (name "unconnected-(CON8-Pad32)") (class "Default")
      (node (ref "CON8") (pin "32") (pinfunction "32_32") (pintype "passive"))
    )
    (net (code "278") (name "unconnected-(CON8-Pad33)") (class "Default")
      (node (ref "CON8") (pin "33") (pinfunction "33_33") (pintype "passive"))
    )
    (net (code "279") (name "unconnected-(CON8-Pad34)") (class "Default")
      (node (ref "CON8") (pin "34") (pinfunction "34_34") (pintype "passive"))
    )
    (net (code "280") (name "unconnected-(CON8-Pad35)") (class "Default")
      (node (ref "CON8") (pin "35") (pinfunction "35_35") (pintype "passive"))
    )
    (net (code "281") (name "unconnected-(CON8-Pad36)") (class "Default")
      (node (ref "CON8") (pin "36") (pinfunction "36_36") (pintype "passive"))
    )
    (net (code "282") (name "unconnected-(CON8-Pad37)") (class "Default")
      (node (ref "CON8") (pin "37") (pinfunction "37_37") (pintype "passive"))
    )
    (net (code "283") (name "unconnected-(CON8-Pad38)") (class "Default")
      (node (ref "CON8") (pin "38") (pinfunction "38_38") (pintype "passive"))
    )
    (net (code "284") (name "unconnected-(CON8-Pad39)") (class "Default")
      (node (ref "CON8") (pin "39") (pinfunction "39_39") (pintype "passive"))
    )
    (net (code "285") (name "unconnected-(CON8-Pad40)") (class "Default")
      (node (ref "CON8") (pin "40") (pinfunction "40_40") (pintype "passive"))
    )
    (net (code "286") (name "unconnected-(CON8-Pad41)") (class "Default")
      (node (ref "CON8") (pin "41") (pinfunction "41_41") (pintype "passive"))
    )
    (net (code "287") (name "unconnected-(CON8-Pad42)") (class "Default")
      (node (ref "CON8") (pin "42") (pinfunction "42_42") (pintype "passive"))
    )
    (net (code "288") (name "unconnected-(CON8-Pad43)") (class "Default")
      (node (ref "CON8") (pin "43") (pinfunction "43_43") (pintype "passive"))
    )
    (net (code "289") (name "unconnected-(CON8-Pad44)") (class "Default")
      (node (ref "CON8") (pin "44") (pinfunction "44_44") (pintype "passive"))
    )
    (net (code "290") (name "unconnected-(CON8-Pad45)") (class "Default")
      (node (ref "CON8") (pin "45") (pinfunction "45_45") (pintype "passive"))
    )
    (net (code "291") (name "unconnected-(CON8-Pad46)") (class "Default")
      (node (ref "CON8") (pin "46") (pinfunction "46_46") (pintype "passive"))
    )
    (net (code "292") (name "unconnected-(CON8-Pad47)") (class "Default")
      (node (ref "CON8") (pin "47") (pinfunction "47_47") (pintype "passive"))
    )
    (net (code "293") (name "unconnected-(CON8-Pad48)") (class "Default")
      (node (ref "CON8") (pin "48") (pinfunction "48_48") (pintype "passive"))
    )
    (net (code "294") (name "unconnected-(CON8-Pad49)") (class "Default")
      (node (ref "CON8") (pin "49") (pinfunction "49_49") (pintype "passive"))
    )
    (net (code "295") (name "unconnected-(CON8-Pad50)") (class "Default")
      (node (ref "CON8") (pin "50") (pinfunction "50_50") (pintype "passive"))
    )
    (net (code "296") (name "unconnected-(CON8-Pad51)") (class "Default")
      (node (ref "CON8") (pin "51") (pinfunction "51_51") (pintype "passive"))
    )
    (net (code "297") (name "unconnected-(CON8-Pad52)") (class "Default")
      (node (ref "CON8") (pin "52") (pinfunction "52_52") (pintype "passive"))
    )
    (net (code "298") (name "unconnected-(CON8-Pad54)") (class "Default")
      (node (ref "CON8") (pin "54") (pinfunction "54_54") (pintype "passive"))
    )
    (net (code "299") (name "unconnected-(CON8-Pad55)") (class "Default")
      (node (ref "CON8") (pin "55") (pinfunction "55_55") (pintype "passive"))
    )
    (net (code "300") (name "unconnected-(CON8-Pad56)") (class "Default")
      (node (ref "CON8") (pin "56") (pinfunction "56_56") (pintype "passive"))
    )
    (net (code "301") (name "unconnected-(CON8-Pad57)") (class "Default")
      (node (ref "CON8") (pin "57") (pinfunction "57_57") (pintype "passive"))
    )
    (net (code "302") (name "unconnected-(CON8-Pad58)") (class "Default")
      (node (ref "CON8") (pin "58") (pinfunction "58_58") (pintype "passive"))
    )
    (net (code "303") (name "unconnected-(CON8-Pad59)") (class "Default")
      (node (ref "CON8") (pin "59") (pinfunction "59_59") (pintype "passive"))
    )
    (net (code "304") (name "unconnected-(CON8-Pad60)") (class "Default")
      (node (ref "CON8") (pin "60") (pinfunction "60_60") (pintype "passive"))
    )
    (net (code "305") (name "unconnected-(CON8-Pad61)") (class "Default")
      (node (ref "CON8") (pin "61") (pinfunction "61_61") (pintype "passive"))
    )
    (net (code "306") (name "unconnected-(CON8-Pad62)") (class "Default")
      (node (ref "CON8") (pin "62") (pinfunction "62_62") (pintype "passive"))
    )
    (net (code "307") (name "unconnected-(CON8-Pad64)") (class "Default")
      (node (ref "CON8") (pin "64") (pinfunction "64_64") (pintype "passive"))
    )
    (net (code "308") (name "unconnected-(CON8-Pad65)") (class "Default")
      (node (ref "CON8") (pin "65") (pinfunction "65_65") (pintype "passive"))
    )
    (net (code "309") (name "unconnected-(CON8-Pad67)") (class "Default")
      (node (ref "CON8") (pin "67") (pinfunction "67_67") (pintype "passive"))
    )
    (net (code "310") (name "unconnected-(CON8-Pad68)") (class "Default")
      (node (ref "CON8") (pin "68") (pinfunction "68_68") (pintype "passive"))
    )
    (net (code "311") (name "unconnected-(CON8-Pad69)") (class "Default")
      (node (ref "CON8") (pin "69") (pinfunction "69_69") (pintype "passive"))
    )
    (net (code "312") (name "unconnected-(CON8-Pad70)") (class "Default")
      (node (ref "CON8") (pin "70") (pinfunction "70_70") (pintype "passive"))
    )
    (net (code "313") (name "unconnected-(CON8-Pad71)") (class "Default")
      (node (ref "CON8") (pin "71") (pinfunction "71_71") (pintype "passive"))
    )
    (net (code "314") (name "unconnected-(CON8-Pad72)") (class "Default")
      (node (ref "CON8") (pin "72") (pinfunction "72_72") (pintype "passive"))
    )
    (net (code "315") (name "unconnected-(CON8-Pad73)") (class "Default")
      (node (ref "CON8") (pin "73") (pinfunction "73_73") (pintype "passive"))
    )
    (net (code "316") (name "unconnected-(CON8-Pad74)") (class "Default")
      (node (ref "CON8") (pin "74") (pinfunction "74_74") (pintype "passive"))
    )
    (net (code "317") (name "unconnected-(U1-PGOOD-Pad8)") (class "Default")
      (node (ref "U1") (pin "8") (pinfunction "PGOOD_8") (pintype "passive+no_connect"))
    )
    (net (code "318") (name "unconnected-(U2-PGOOD-Pad8)") (class "Default")
      (node (ref "U2") (pin "8") (pinfunction "PGOOD_8") (pintype "passive+no_connect"))
    )
    (net (code "319") (name "unconnected-(U4-R2IN-Pad8)") (class "Default")
      (node (ref "U4") (pin "8") (pinfunction "R2IN_8") (pintype "passive+no_connect"))
    )
    (net (code "320") (name "unconnected-(U4-R2OUT-Pad9)") (class "Default")
      (node (ref "U4") (pin "9") (pinfunction "R2OUT_9") (pintype "passive+no_connect"))
    )
    (net (code "321") (name "unconnected-(U4-T2IN-Pad10)") (class "Default")
      (node (ref "U4") (pin "10") (pinfunction "T2IN_10") (pintype "passive+no_connect"))
    )
    (net (code "322") (name "unconnected-(U4-T2OUT-Pad7)") (class "Default")
      (node (ref "U4") (pin "7") (pinfunction "T2OUT_7") (pintype "passive+no_connect"))
    )
    (net (code "323") (name "unconnected-(U7-A2-Pad4)") (class "Default")
      (node (ref "U7") (pin "4") (pinfunction "A2_4") (pintype "passive+no_connect"))
    )
    (net (code "324") (name "unconnected-(U7-B2-Pad1)") (class "Default")
      (node (ref "U7") (pin "1") (pinfunction "B2_1") (pintype "passive+no_connect"))
    )
  )
)
